# A314B2.net
KiCad netlist of a schematic drawn in EAGLE
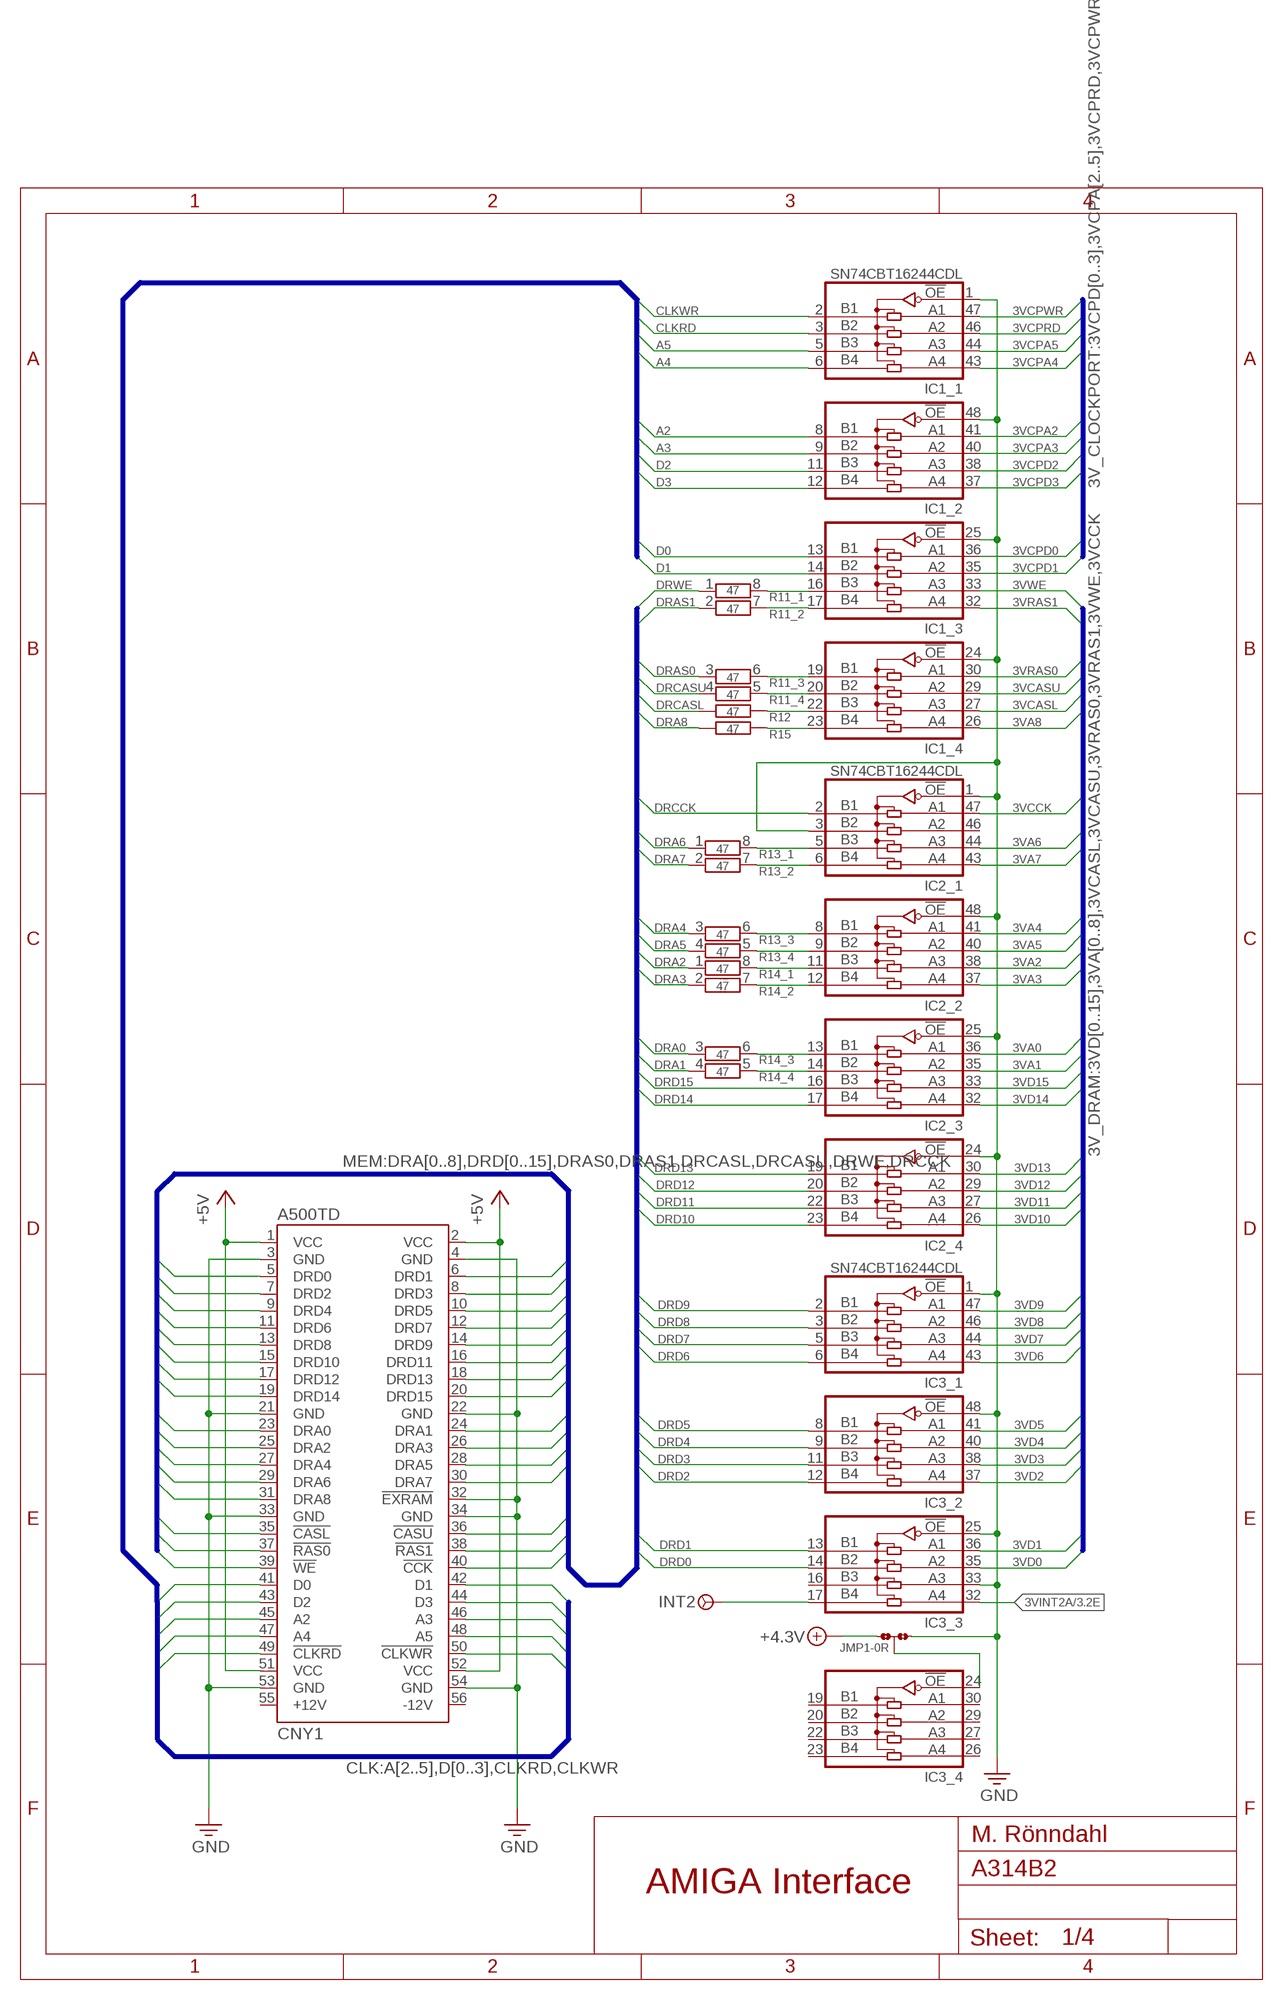
[diagram p0: schematic, sheet 1]
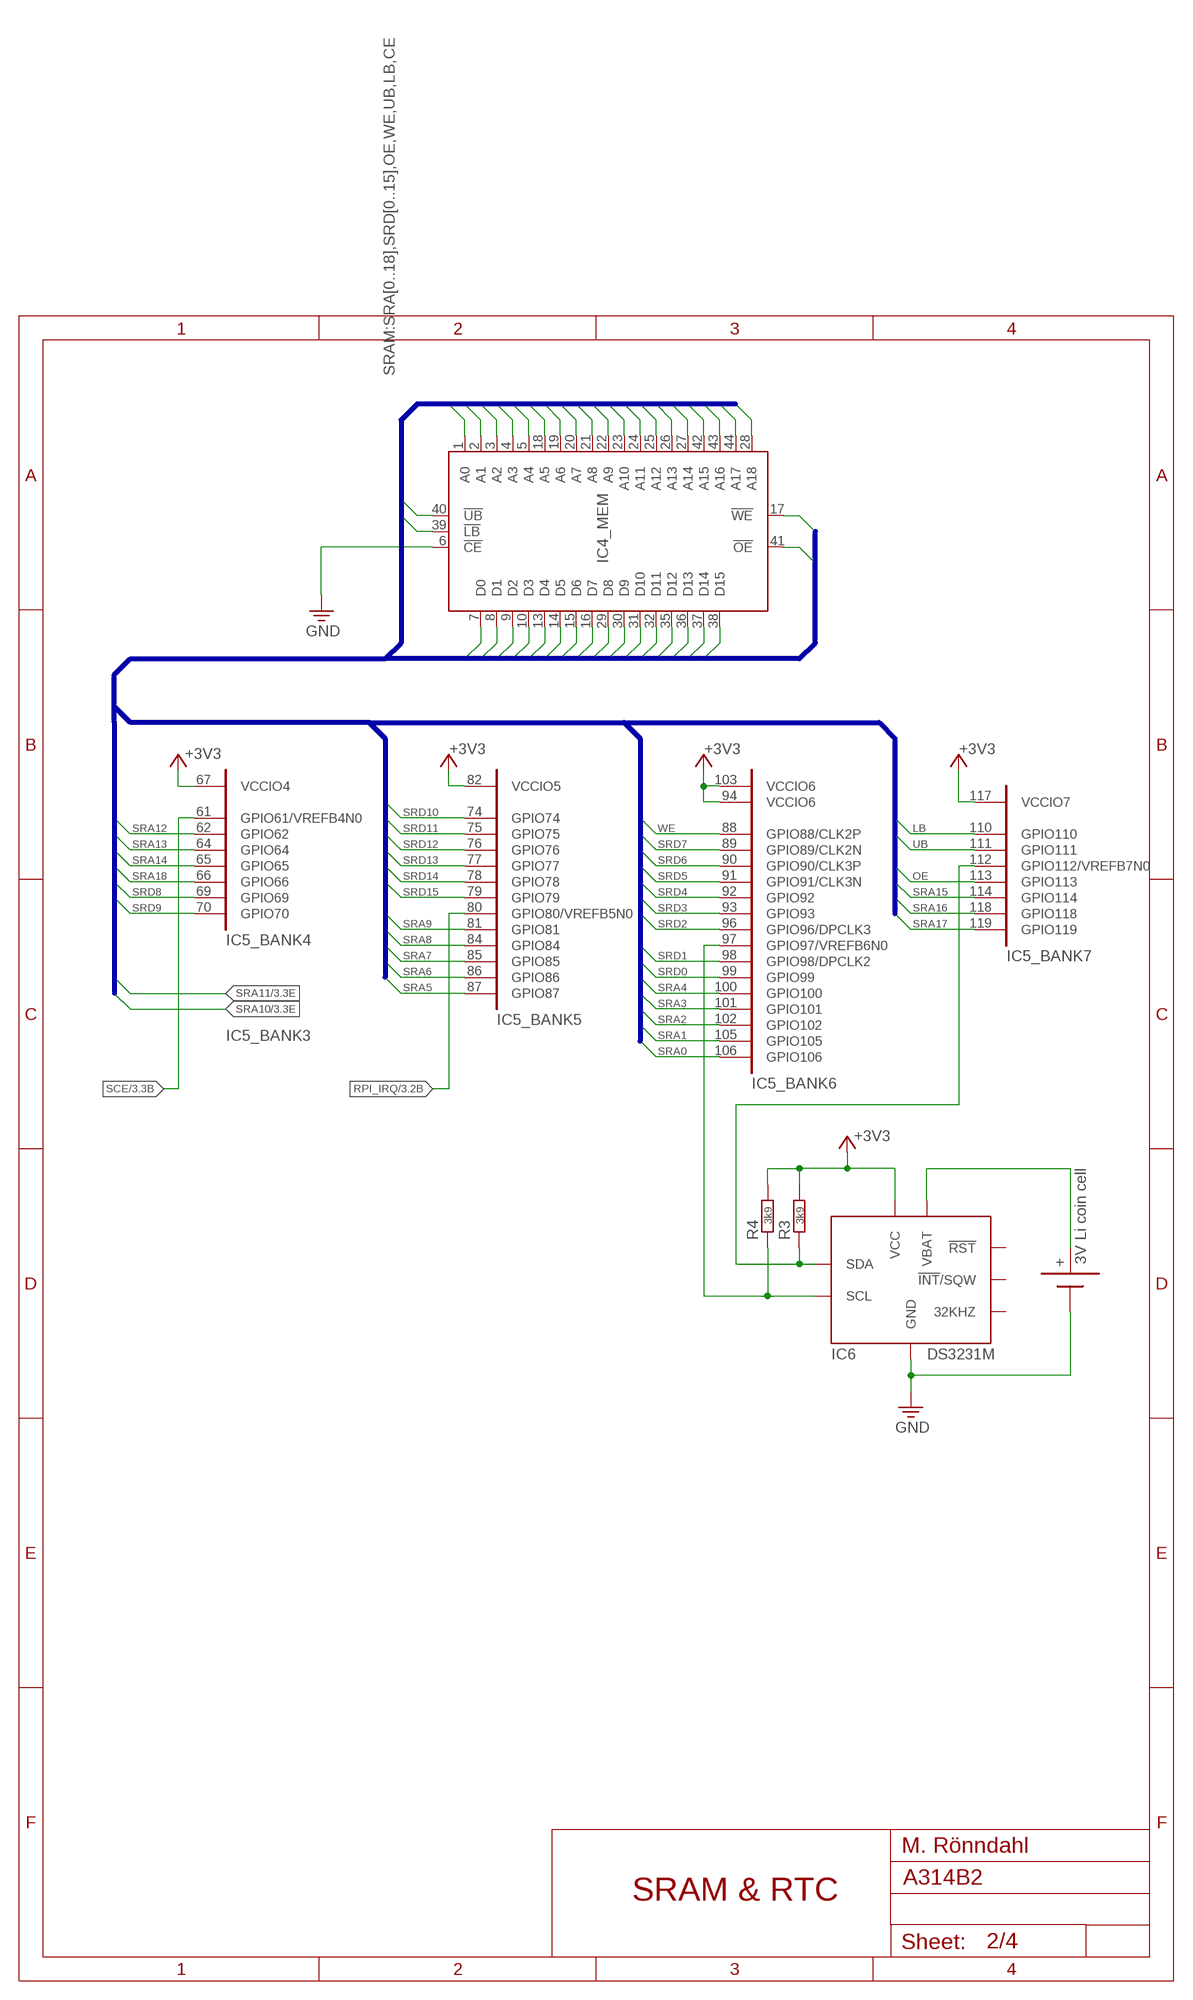
[diagram p1: schematic, sheet 2]
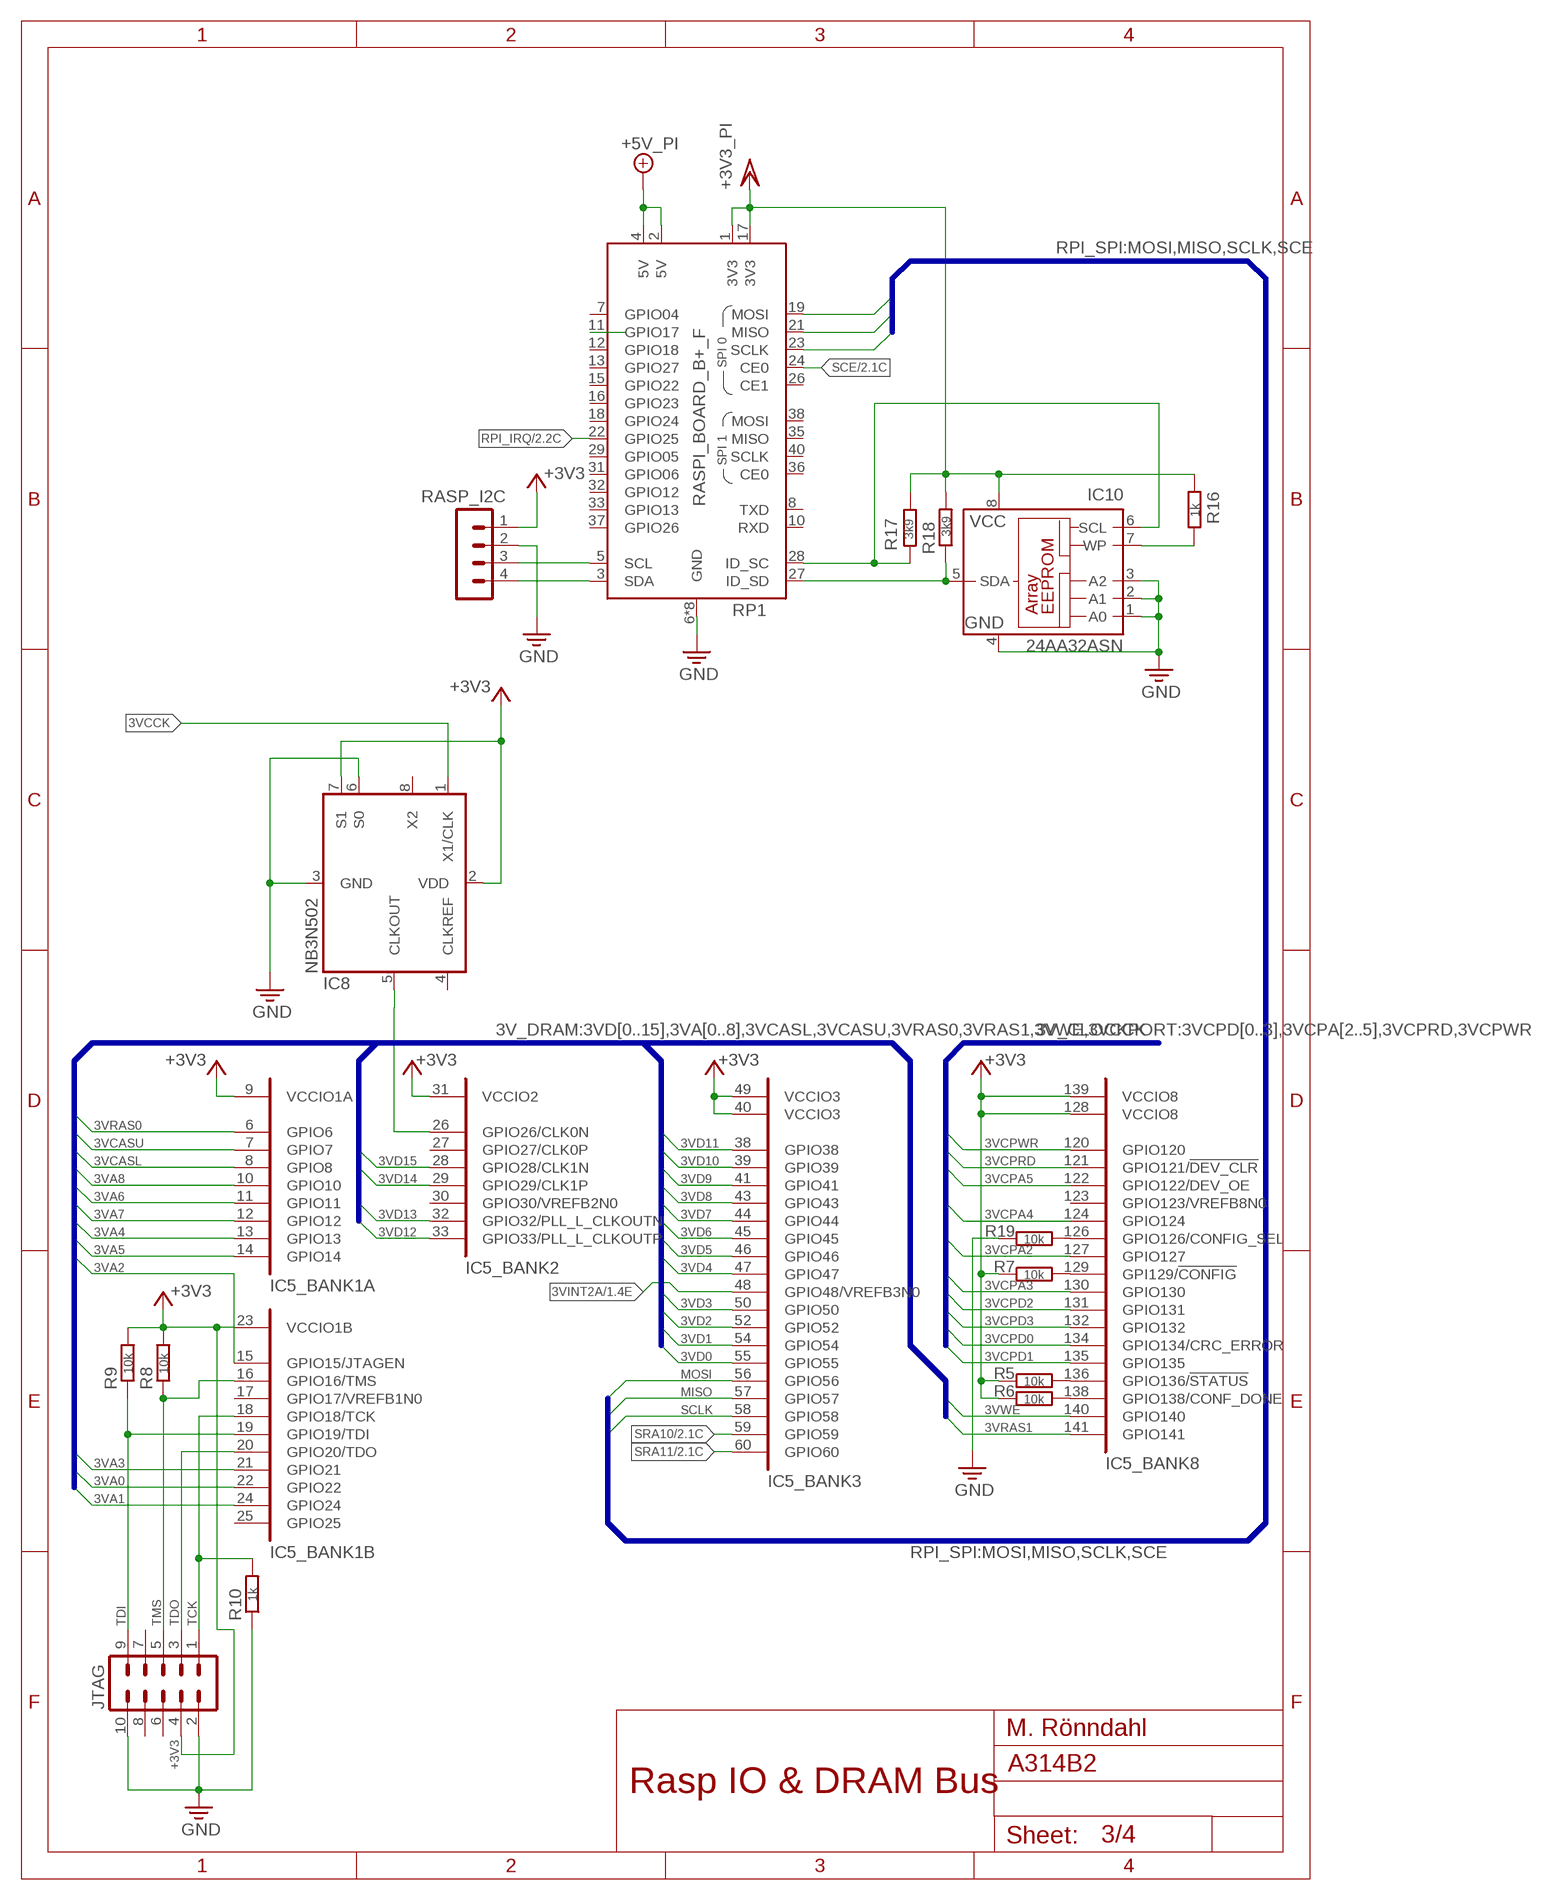
[diagram p2: schematic, sheet 3]
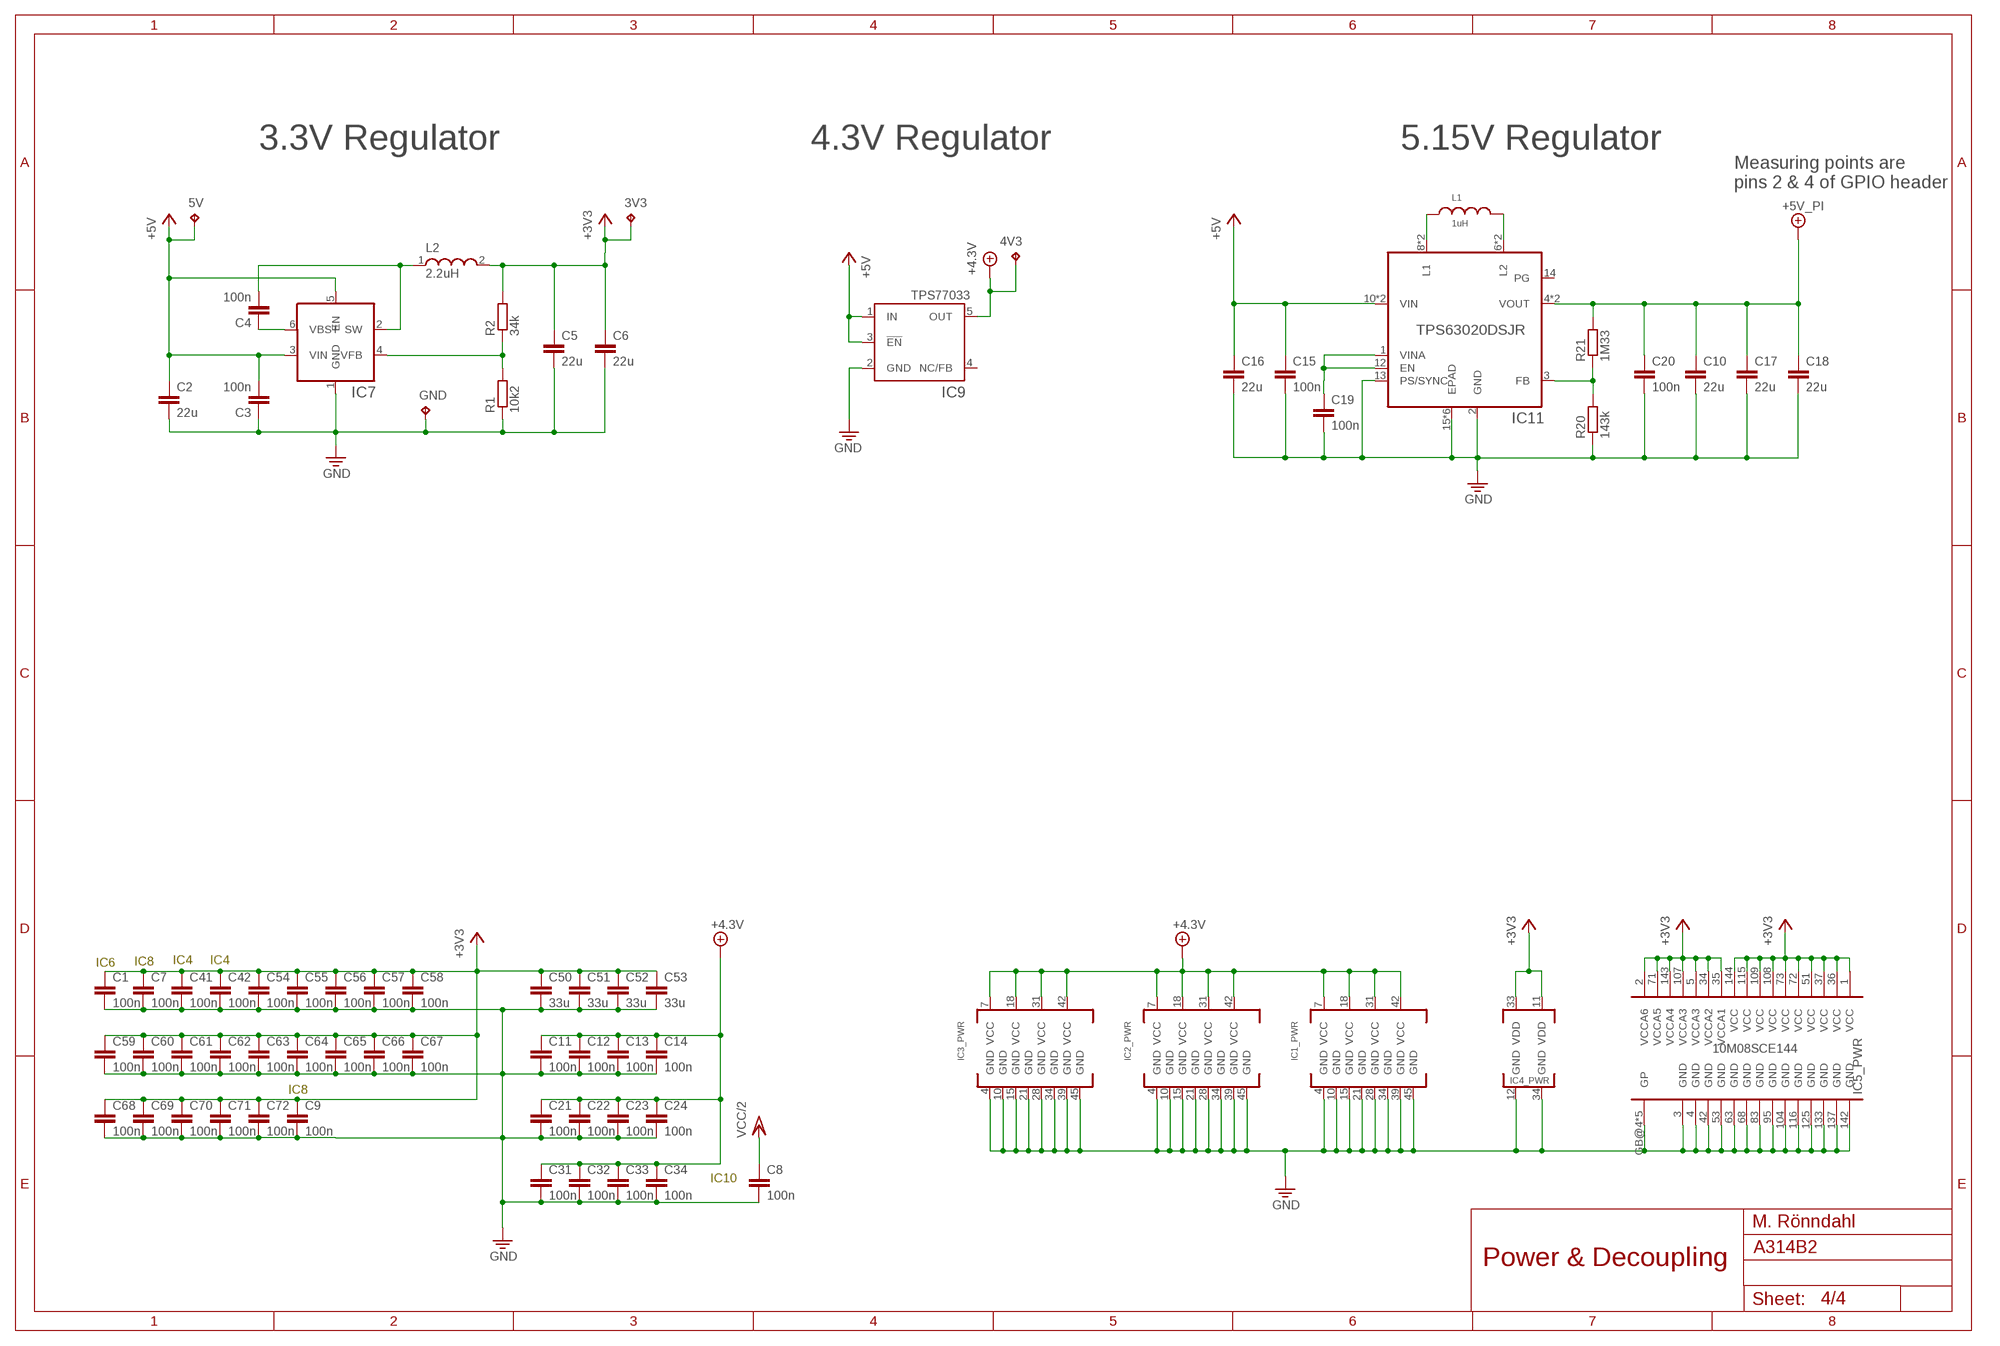
[diagram p3: schematic, sheet 4]

(export (version "E")
  (design (tool "Eeschema 10.0.6"))
  (components
    (comp (ref "CNY1")
      (value "A500TD")
      (footprint "eagle-import:TRAPDOOR")
      (libsource (lib "eagle-import") (part "A500TD"))
    )
    (comp (ref "IC1")
      (value "SN74CBT16244CDL")
      (footprint "eagle-import:SSOP-DL48")
      (libsource (lib "eagle-import") (part "SN74CBT16244CDL"))
    )
    (comp (ref "IC2")
      (value "SN74CBT16244CDL")
      (footprint "eagle-import:SSOP-DL48")
      (libsource (lib "eagle-import") (part "SN74CBT16244CDL"))
    )
    (comp (ref "IC3")
      (value "SN74CBT16244CDL")
      (footprint "eagle-import:SSOP-DL48")
      (libsource (lib "eagle-import") (part "SN74CBT16244CDL"))
    )
    (comp (ref "INT2")
      (value "TP1")
      (footprint "eagle-import:P1-08")
      (libsource (lib "eagle-import") (part "TP_LITE"))
    )
    (comp (ref "JMP1")
      (value "0R-JUMPC")
      (footprint "eagle-import:C0R-JMP")
      (libsource (lib "eagle-import") (part "0R-JUMPC"))
    )
    (comp (ref "R11")
      (value "47")
      (footprint "eagle-import:CTS742C083")
      (libsource (lib "eagle-import") (part "CTS742C083_S"))
    )
    (comp (ref "R12")
      (value "47")
      (footprint "eagle-import:R0805")
      (libsource (lib "eagle-import") (part "R-EU_R0805"))
    )
    (comp (ref "R13")
      (value "47")
      (footprint "eagle-import:CTS742C083")
      (libsource (lib "eagle-import") (part "CTS742C083_S"))
    )
    (comp (ref "R14")
      (value "47")
      (footprint "eagle-import:CTS742C083")
      (libsource (lib "eagle-import") (part "CTS742C083_S"))
    )
    (comp (ref "R15")
      (value "47")
      (footprint "eagle-import:R0805")
      (libsource (lib "eagle-import") (part "R-EU_R0805"))
    )
    (comp (ref "3V3")
      (value "TPPAD1-13")
      (footprint "eagle-import:P1-13")
      (libsource (lib "eagle-import") (part "TPPAD1-13"))
    )
    (comp (ref "4V3")
      (value "TPPAD1-13")
      (footprint "eagle-import:P1-13")
      (libsource (lib "eagle-import") (part "TPPAD1-13"))
    )
    (comp (ref "5V")
      (value "TPPAD1-13")
      (footprint "eagle-import:P1-13")
      (libsource (lib "eagle-import") (part "TPPAD1-13"))
    )
    (comp (ref "C1")
      (value "100n")
      (footprint "eagle-import:C0805")
      (libsource (lib "eagle-import") (part "C-EUC0805"))
    )
    (comp (ref "C2")
      (value "22u")
      (footprint "eagle-import:C1812K")
      (libsource (lib "eagle-import") (part "C-EUC1812K"))
    )
    (comp (ref "C3")
      (value "100n")
      (footprint "eagle-import:C0805")
      (libsource (lib "eagle-import") (part "C-EUC0805"))
    )
    (comp (ref "C4")
      (value "100n")
      (footprint "eagle-import:C0805")
      (libsource (lib "eagle-import") (part "C-EUC0805"))
    )
    (comp (ref "C5")
      (value "22u")
      (footprint "eagle-import:C1812K")
      (libsource (lib "eagle-import") (part "C-EUC1812K"))
    )
    (comp (ref "C6")
      (value "22u")
      (footprint "eagle-import:C1812K")
      (libsource (lib "eagle-import") (part "C-EUC1812K"))
    )
    (comp (ref "C7")
      (value "100n")
      (footprint "eagle-import:C0805")
      (libsource (lib "eagle-import") (part "C-EUC0805"))
    )
    (comp (ref "C8")
      (value "100n")
      (footprint "eagle-import:C0805")
      (libsource (lib "eagle-import") (part "C-EUC0805"))
    )
    (comp (ref "C9")
      (value "100n")
      (footprint "eagle-import:C0805")
      (libsource (lib "eagle-import") (part "C-EUC0805"))
    )
    (comp (ref "C10")
      (value "22u")
      (footprint "eagle-import:C1812K")
      (libsource (lib "eagle-import") (part "C-EUC1812K"))
    )
    (comp (ref "C11")
      (value "100n")
      (footprint "eagle-import:C0805")
      (libsource (lib "eagle-import") (part "C-EUC0805"))
    )
    (comp (ref "C12")
      (value "100n")
      (footprint "eagle-import:C0805")
      (libsource (lib "eagle-import") (part "C-EUC0805"))
    )
    (comp (ref "C13")
      (value "100n")
      (footprint "eagle-import:C0805")
      (libsource (lib "eagle-import") (part "C-EUC0805"))
    )
    (comp (ref "C14")
      (value "100n")
      (footprint "eagle-import:C0805")
      (libsource (lib "eagle-import") (part "C-EUC0805"))
    )
    (comp (ref "C15")
      (value "100n")
      (footprint "eagle-import:C0805")
      (libsource (lib "eagle-import") (part "C-EUC0805"))
    )
    (comp (ref "C16")
      (value "22u")
      (footprint "eagle-import:C1812K")
      (libsource (lib "eagle-import") (part "C-EUC1812K"))
    )
    (comp (ref "C17")
      (value "22u")
      (footprint "eagle-import:C1812K")
      (libsource (lib "eagle-import") (part "C-EUC1812K"))
    )
    (comp (ref "C18")
      (value "22u")
      (footprint "eagle-import:C1812K")
      (libsource (lib "eagle-import") (part "C-EUC1812K"))
    )
    (comp (ref "C19")
      (value "100n")
      (footprint "eagle-import:C0805")
      (libsource (lib "eagle-import") (part "C-EUC0805"))
    )
    (comp (ref "C20")
      (value "100n")
      (footprint "eagle-import:C0805")
      (libsource (lib "eagle-import") (part "C-EUC0805"))
    )
    (comp (ref "C21")
      (value "100n")
      (footprint "eagle-import:C0805")
      (libsource (lib "eagle-import") (part "C-EUC0805"))
    )
    (comp (ref "C22")
      (value "100n")
      (footprint "eagle-import:C0805")
      (libsource (lib "eagle-import") (part "C-EUC0805"))
    )
    (comp (ref "C23")
      (value "100n")
      (footprint "eagle-import:C0805")
      (libsource (lib "eagle-import") (part "C-EUC0805"))
    )
    (comp (ref "C24")
      (value "100n")
      (footprint "eagle-import:C0805")
      (libsource (lib "eagle-import") (part "C-EUC0805"))
    )
    (comp (ref "C31")
      (value "100n")
      (footprint "eagle-import:C0805")
      (libsource (lib "eagle-import") (part "C-EUC0805"))
    )
    (comp (ref "C32")
      (value "100n")
      (footprint "eagle-import:C0805")
      (libsource (lib "eagle-import") (part "C-EUC0805"))
    )
    (comp (ref "C33")
      (value "100n")
      (footprint "eagle-import:C0805")
      (libsource (lib "eagle-import") (part "C-EUC0805"))
    )
    (comp (ref "C34")
      (value "100n")
      (footprint "eagle-import:C0805")
      (libsource (lib "eagle-import") (part "C-EUC0805"))
    )
    (comp (ref "C41")
      (value "100n")
      (footprint "eagle-import:C0805")
      (libsource (lib "eagle-import") (part "C-EUC0805"))
    )
    (comp (ref "C42")
      (value "100n")
      (footprint "eagle-import:C0805")
      (libsource (lib "eagle-import") (part "C-EUC0805"))
    )
    (comp (ref "C50")
      (value "33u")
      (footprint "eagle-import:C0805")
      (libsource (lib "eagle-import") (part "C-EUC0805"))
    )
    (comp (ref "C51")
      (value "33u")
      (footprint "eagle-import:C0805")
      (libsource (lib "eagle-import") (part "C-EUC0805"))
    )
    (comp (ref "C52")
      (value "33u")
      (footprint "eagle-import:C0805")
      (libsource (lib "eagle-import") (part "C-EUC0805"))
    )
    (comp (ref "C53")
      (value "33u")
      (footprint "eagle-import:C0805")
      (libsource (lib "eagle-import") (part "C-EUC0805"))
    )
    (comp (ref "C54")
      (value "100n")
      (footprint "eagle-import:C0805")
      (libsource (lib "eagle-import") (part "C-EUC0805"))
    )
    (comp (ref "C55")
      (value "100n")
      (footprint "eagle-import:C0805")
      (libsource (lib "eagle-import") (part "C-EUC0805"))
    )
    (comp (ref "C56")
      (value "100n")
      (footprint "eagle-import:C0805")
      (libsource (lib "eagle-import") (part "C-EUC0805"))
    )
    (comp (ref "C57")
      (value "100n")
      (footprint "eagle-import:C0805")
      (libsource (lib "eagle-import") (part "C-EUC0805"))
    )
    (comp (ref "C58")
      (value "100n")
      (footprint "eagle-import:C0805")
      (libsource (lib "eagle-import") (part "C-EUC0805"))
    )
    (comp (ref "C59")
      (value "100n")
      (footprint "eagle-import:C0805")
      (libsource (lib "eagle-import") (part "C-EUC0805"))
    )
    (comp (ref "C60")
      (value "100n")
      (footprint "eagle-import:C0805")
      (libsource (lib "eagle-import") (part "C-EUC0805"))
    )
    (comp (ref "C61")
      (value "100n")
      (footprint "eagle-import:C0805")
      (libsource (lib "eagle-import") (part "C-EUC0805"))
    )
    (comp (ref "C62")
      (value "100n")
      (footprint "eagle-import:C0805")
      (libsource (lib "eagle-import") (part "C-EUC0805"))
    )
    (comp (ref "C63")
      (value "100n")
      (footprint "eagle-import:C0805")
      (libsource (lib "eagle-import") (part "C-EUC0805"))
    )
    (comp (ref "C64")
      (value "100n")
      (footprint "eagle-import:C0805")
      (libsource (lib "eagle-import") (part "C-EUC0805"))
    )
    (comp (ref "C65")
      (value "100n")
      (footprint "eagle-import:C0805")
      (libsource (lib "eagle-import") (part "C-EUC0805"))
    )
    (comp (ref "C66")
      (value "100n")
      (footprint "eagle-import:C0805")
      (libsource (lib "eagle-import") (part "C-EUC0805"))
    )
    (comp (ref "C67")
      (value "100n")
      (footprint "eagle-import:C0805")
      (libsource (lib "eagle-import") (part "C-EUC0805"))
    )
    (comp (ref "C68")
      (value "100n")
      (footprint "eagle-import:C0805")
      (libsource (lib "eagle-import") (part "C-EUC0805"))
    )
    (comp (ref "C69")
      (value "100n")
      (footprint "eagle-import:C0805")
      (libsource (lib "eagle-import") (part "C-EUC0805"))
    )
    (comp (ref "C70")
      (value "100n")
      (footprint "eagle-import:C0805")
      (libsource (lib "eagle-import") (part "C-EUC0805"))
    )
    (comp (ref "C71")
      (value "100n")
      (footprint "eagle-import:C0805")
      (libsource (lib "eagle-import") (part "C-EUC0805"))
    )
    (comp (ref "C72")
      (value "100n")
      (footprint "eagle-import:C0805")
      (libsource (lib "eagle-import") (part "C-EUC0805"))
    )
    (comp (ref "GND")
      (value "TPPAD1-13")
      (footprint "eagle-import:P1-13")
      (libsource (lib "eagle-import") (part "TPPAD1-13"))
    )
    (comp (ref "IC4")
      (value "IS61WV51216BLL-10TLI")
      (footprint "eagle-import:TSOP-2")
      (libsource (lib "eagle-import") (part "IS61WV51216BLL-10TLI"))
    )
    (comp (ref "IC5")
      (value "10M08SCE144")
      (footprint "eagle-import:SQFP-S-20X20-144")
      (libsource (lib "eagle-import") (part "10M08SCE144"))
    )
    (comp (ref "IC7")
      (value "TPS565208DDC")
      (footprint "eagle-import:THIN_SO23")
      (libsource (lib "eagle-import") (part "TPS565208DDC"))
    )
    (comp (ref "IC9")
      (value "TPS77033")
      (footprint "eagle-import:SOT23-DBV")
      (fields (field (name "MF") "TEXAS INSTRUMENTS") (field (name "MPN") "TPS77033DBVT"))
      (libsource (lib "eagle-import") (part "TPS77033"))
    )
    (comp (ref "IC11")
      (value "TPS63020DSJR")
      (footprint "eagle-import:DSJ14_2P85X1P58")
      (libsource (lib "eagle-import") (part "TPS63020DSJR"))
    )
    (comp (ref "L1")
      (value "1uH")
      (footprint "eagle-import:WE-TPC_6823")
      (libsource (lib "eagle-import") (part "WE-TPC_6823_744062001"))
    )
    (comp (ref "L2")
      (value "2.2uH")
      (footprint "eagle-import:WE-TPC_1028_1038")
      (libsource (lib "eagle-import") (part "WE-TPC_1028/1038"))
    )
    (comp (ref "R1")
      (value "10k2")
      (footprint "eagle-import:R0805")
      (libsource (lib "eagle-import") (part "R-EU_R0805"))
    )
    (comp (ref "R2")
      (value "34k")
      (footprint "eagle-import:R0805")
      (libsource (lib "eagle-import") (part "R-EU_R0805"))
    )
    (comp (ref "R20")
      (value "143k")
      (footprint "eagle-import:R0805")
      (libsource (lib "eagle-import") (part "R-EU_R0805"))
    )
    (comp (ref "R21")
      (value "1M33")
      (footprint "eagle-import:R0805")
      (libsource (lib "eagle-import") (part "R-EU_R0805"))
    )
    (comp (ref "IC8")
      (value "NB3N502")
      (footprint "eagle-import:SO08")
      (libsource (lib "eagle-import") (part "NB3N502"))
    )
    (comp (ref "IC10")
      (value "24AA32ASN")
      (footprint "eagle-import:SO-08")
      (fields (field (name "MF") "MICROCHIP") (field (name "MPN") "24AA32A-I/SN"))
      (libsource (lib "eagle-import") (part "24SNAA32A"))
    )
    (comp (ref "JTAG")
      (value "MA05-2")
      (footprint "eagle-import:MA05-2")
      (libsource (lib "eagle-import") (part "MA05-2"))
    )
    (comp (ref "R5")
      (value "10k")
      (footprint "eagle-import:R0805")
      (libsource (lib "eagle-import") (part "R-EU_R0805"))
    )
    (comp (ref "R6")
      (value "10k")
      (footprint "eagle-import:R0805")
      (libsource (lib "eagle-import") (part "R-EU_R0805"))
    )
    (comp (ref "R7")
      (value "10k")
      (footprint "eagle-import:R0805")
      (libsource (lib "eagle-import") (part "R-EU_R0805"))
    )
    (comp (ref "R8")
      (value "10k")
      (footprint "eagle-import:R0805")
      (libsource (lib "eagle-import") (part "R-EU_R0805"))
    )
    (comp (ref "R9")
      (value "10k")
      (footprint "eagle-import:R0805")
      (libsource (lib "eagle-import") (part "R-EU_R0805"))
    )
    (comp (ref "R10")
      (value "1k")
      (footprint "eagle-import:R0805")
      (libsource (lib "eagle-import") (part "R-EU_R0805"))
    )
    (comp (ref "R16")
      (value "1k")
      (footprint "eagle-import:R0805")
      (libsource (lib "eagle-import") (part "R-EU_R0805"))
    )
    (comp (ref "R17")
      (value "3k9")
      (footprint "eagle-import:R0805")
      (libsource (lib "eagle-import") (part "R-EU_R0805"))
    )
    (comp (ref "R18")
      (value "3k9")
      (footprint "eagle-import:R0805")
      (libsource (lib "eagle-import") (part "R-EU_R0805"))
    )
    (comp (ref "R19")
      (value "10k")
      (footprint "eagle-import:R0805")
      (libsource (lib "eagle-import") (part "R-EU_R0805"))
    )
    (comp (ref "RASP_I2C")
      (value "MA04-1")
      (footprint "eagle-import:MA04-1")
      (libsource (lib "eagle-import") (part "MA04-1"))
    )
    (comp (ref "RP1")
      (value "RASPI_BOARD_B+_F")
      (footprint "eagle-import:RASPI_BOARD_B+_FULL")
      (libsource (lib "eagle-import") (part "RASPI_BOARD_B+_F"))
    )
    (comp (ref "BAT1")
      (value "CR2025/CR2032TH")
      (footprint "eagle-import:LINX20XX-THM")
      (libsource (lib "eagle-import") (part "CR2025/CR2032TH"))
    )
    (comp (ref "IC6")
      (value "DS3231M")
      (footprint "eagle-import:SOIC8")
      (libsource (lib "eagle-import") (part "DS3231M"))
    )
    (comp (ref "R3")
      (value "3k9")
      (footprint "eagle-import:R0805")
      (libsource (lib "eagle-import") (part "R-EU_R0805"))
    )
    (comp (ref "R4")
      (value "3k9")
      (footprint "eagle-import:R0805")
      (libsource (lib "eagle-import") (part "R-EU_R0805"))
    )
  )
  (nets
    (net (code "3") (name "+3V3") (class "Default")
      (node (ref "3V3") (pin "TP") (pinfunction "TP_TP") (pintype "input"))
      (node (ref "C1") (pin "1") (pinfunction "1_1") (pintype "passive"))
      (node (ref "C41") (pin "1") (pinfunction "1_1") (pintype "passive"))
      (node (ref "C42") (pin "1") (pinfunction "1_1") (pintype "passive"))
      (node (ref "C5") (pin "1") (pinfunction "1_1") (pintype "passive"))
      (node (ref "C50") (pin "1") (pinfunction "1_1") (pintype "passive"))
      (node (ref "C51") (pin "1") (pinfunction "1_1") (pintype "passive"))
      (node (ref "C52") (pin "1") (pinfunction "1_1") (pintype "passive"))
      (node (ref "C53") (pin "1") (pinfunction "1_1") (pintype "passive"))
      (node (ref "C54") (pin "1") (pinfunction "1_1") (pintype "passive"))
      (node (ref "C55") (pin "1") (pinfunction "1_1") (pintype "passive"))
      (node (ref "C56") (pin "1") (pinfunction "1_1") (pintype "passive"))
      (node (ref "C57") (pin "1") (pinfunction "1_1") (pintype "passive"))
      (node (ref "C58") (pin "1") (pinfunction "1_1") (pintype "passive"))
      (node (ref "C59") (pin "1") (pinfunction "1_1") (pintype "passive"))
      (node (ref "C6") (pin "1") (pinfunction "1_1") (pintype "passive"))
      (node (ref "C60") (pin "1") (pinfunction "1_1") (pintype "passive"))
      (node (ref "C61") (pin "1") (pinfunction "1_1") (pintype "passive"))
      (node (ref "C62") (pin "1") (pinfunction "1_1") (pintype "passive"))
      (node (ref "C63") (pin "1") (pinfunction "1_1") (pintype "passive"))
      (node (ref "C64") (pin "1") (pinfunction "1_1") (pintype "passive"))
      (node (ref "C65") (pin "1") (pinfunction "1_1") (pintype "passive"))
      (node (ref "C66") (pin "1") (pinfunction "1_1") (pintype "passive"))
      (node (ref "C67") (pin "1") (pinfunction "1_1") (pintype "passive"))
      (node (ref "C68") (pin "1") (pinfunction "1_1") (pintype "passive"))
      (node (ref "C69") (pin "1") (pinfunction "1_1") (pintype "passive"))
      (node (ref "C7") (pin "1") (pinfunction "1_1") (pintype "passive"))
      (node (ref "C70") (pin "1") (pinfunction "1_1") (pintype "passive"))
      (node (ref "C71") (pin "1") (pinfunction "1_1") (pintype "passive"))
      (node (ref "C72") (pin "1") (pinfunction "1_1") (pintype "passive"))
      (node (ref "C9") (pin "1") (pinfunction "1_1") (pintype "passive"))
      (node (ref "IC4") (pin "11") (pinfunction "VDD_11") (pintype "bidirectional"))
      (node (ref "IC4") (pin "33") (pinfunction "VDD_33") (pintype "bidirectional"))
      (node (ref "IC5") (pin "1") (pinfunction "VCC_1") (pintype "power_in"))
      (node (ref "IC5") (pin "103") (pinfunction "VCCIO6_103") (pintype "power_in"))
      (node (ref "IC5") (pin "107") (pinfunction "VCCA3_107") (pintype "power_in"))
      (node (ref "IC5") (pin "108") (pinfunction "VCC_108") (pintype "power_in"))
      (node (ref "IC5") (pin "109") (pinfunction "VCC_109") (pintype "power_in"))
      (node (ref "IC5") (pin "115") (pinfunction "VCC_115") (pintype "power_in"))
      (node (ref "IC5") (pin "117") (pinfunction "VCCIO7_117") (pintype "power_in"))
      (node (ref "IC5") (pin "128") (pinfunction "VCCIO8_128") (pintype "power_in"))
      (node (ref "IC5") (pin "139") (pinfunction "VCCIO8_139") (pintype "power_in"))
      (node (ref "IC5") (pin "143") (pinfunction "VCCA4_143") (pintype "power_in"))
      (node (ref "IC5") (pin "144") (pinfunction "VCC_144") (pintype "power_in"))
      (node (ref "IC5") (pin "2") (pinfunction "VCCA6_2") (pintype "power_in"))
      (node (ref "IC5") (pin "23") (pinfunction "VCCIO1B_23") (pintype "power_in"))
      (node (ref "IC5") (pin "31") (pinfunction "VCCIO2_31") (pintype "power_in"))
      (node (ref "IC5") (pin "34") (pinfunction "VCCA2_34") (pintype "power_in"))
      (node (ref "IC5") (pin "35") (pinfunction "VCCA1_35") (pintype "power_in"))
      (node (ref "IC5") (pin "36") (pinfunction "VCC_36") (pintype "power_in"))
      (node (ref "IC5") (pin "37") (pinfunction "VCC_37") (pintype "power_in"))
      (node (ref "IC5") (pin "40") (pinfunction "VCCIO3_40") (pintype "power_in"))
      (node (ref "IC5") (pin "49") (pinfunction "VCCIO3_49") (pintype "power_in"))
      (node (ref "IC5") (pin "5") (pinfunction "VCCA3_5") (pintype "power_in"))
      (node (ref "IC5") (pin "51") (pinfunction "VCC_51") (pintype "power_in"))
      (node (ref "IC5") (pin "67") (pinfunction "VCCIO4_67") (pintype "power_in"))
      (node (ref "IC5") (pin "71") (pinfunction "VCCA5_71") (pintype "power_in"))
      (node (ref "IC5") (pin "72") (pinfunction "VCC_72") (pintype "power_in"))
      (node (ref "IC5") (pin "73") (pinfunction "VCC_73") (pintype "power_in"))
      (node (ref "IC5") (pin "82") (pinfunction "VCCIO5_82") (pintype "power_in"))
      (node (ref "IC5") (pin "9") (pinfunction "VCCIO1A_9") (pintype "power_in"))
      (node (ref "IC5") (pin "94") (pinfunction "VCCIO6_94") (pintype "power_in"))
      (node (ref "IC6") (pin "2") (pinfunction "VCC_2") (pintype "power_in"))
      (node (ref "IC8") (pin "2") (pinfunction "VDD_2") (pintype "power_in"))
      (node (ref "IC8") (pin "7") (pinfunction "S1_7") (pintype "input"))
      (node (ref "JTAG") (pin "4") (pinfunction "4_4") (pintype "passive"))
      (node (ref "L2") (pin "2") (pinfunction "2_2") (pintype "passive"))
      (node (ref "R2") (pin "2") (pinfunction "2_2") (pintype "passive"))
      (node (ref "R3") (pin "2") (pinfunction "2_2") (pintype "passive"))
      (node (ref "R4") (pin "2") (pinfunction "2_2") (pintype "passive"))
      (node (ref "R5") (pin "1") (pinfunction "1_1") (pintype "passive"))
      (node (ref "R6") (pin "1") (pinfunction "1_1") (pintype "passive"))
      (node (ref "R7") (pin "1") (pinfunction "1_1") (pintype "passive"))
      (node (ref "R8") (pin "2") (pinfunction "2_2") (pintype "passive"))
      (node (ref "R9") (pin "2") (pinfunction "2_2") (pintype "passive"))
      (node (ref "RASP_I2C") (pin "1") (pinfunction "1_1") (pintype "passive"))
    )
    (net (code "4") (name "+4.3V") (class "Default")
      (node (ref "4V3") (pin "TP") (pinfunction "TP_TP") (pintype "input"))
      (node (ref "C11") (pin "1") (pinfunction "1_1") (pintype "passive"))
      (node (ref "C12") (pin "1") (pinfunction "1_1") (pintype "passive"))
      (node (ref "C13") (pin "1") (pinfunction "1_1") (pintype "passive"))
      (node (ref "C14") (pin "1") (pinfunction "1_1") (pintype "passive"))
      (node (ref "C21") (pin "1") (pinfunction "1_1") (pintype "passive"))
      (node (ref "C22") (pin "1") (pinfunction "1_1") (pintype "passive"))
      (node (ref "C23") (pin "1") (pinfunction "1_1") (pintype "passive"))
      (node (ref "C24") (pin "1") (pinfunction "1_1") (pintype "passive"))
      (node (ref "C31") (pin "1") (pinfunction "1_1") (pintype "passive"))
      (node (ref "C32") (pin "1") (pinfunction "1_1") (pintype "passive"))
      (node (ref "C33") (pin "1") (pinfunction "1_1") (pintype "passive"))
      (node (ref "C34") (pin "1") (pinfunction "1_1") (pintype "passive"))
      (node (ref "IC1") (pin "18") (pinfunction "VCC_18") (pintype "power_in"))
      (node (ref "IC1") (pin "31") (pinfunction "VCC_31") (pintype "power_in"))
      (node (ref "IC1") (pin "42") (pinfunction "VCC_42") (pintype "power_in"))
      (node (ref "IC1") (pin "7") (pinfunction "VCC_7") (pintype "power_in"))
      (node (ref "IC2") (pin "18") (pinfunction "VCC_18") (pintype "power_in"))
      (node (ref "IC2") (pin "31") (pinfunction "VCC_31") (pintype "power_in"))
      (node (ref "IC2") (pin "42") (pinfunction "VCC_42") (pintype "power_in"))
      (node (ref "IC2") (pin "7") (pinfunction "VCC_7") (pintype "power_in"))
      (node (ref "IC3") (pin "18") (pinfunction "VCC_18") (pintype "power_in"))
      (node (ref "IC3") (pin "24") (pinfunction "~{OE}_24") (pintype "input"))
      (node (ref "IC3") (pin "31") (pinfunction "VCC_31") (pintype "power_in"))
      (node (ref "IC3") (pin "42") (pinfunction "VCC_42") (pintype "power_in"))
      (node (ref "IC3") (pin "7") (pinfunction "VCC_7") (pintype "power_in"))
      (node (ref "IC9") (pin "5") (pinfunction "OUT_5") (pintype "passive"))
      (node (ref "JMP1") (pin "1") (pinfunction "1_1") (pintype "passive"))
      (node (ref "JMP1") (pin "2") (pinfunction "2_2") (pintype "passive"))
    )
    (net (code "5") (name "+5V") (class "Default")
      (node (ref "5V") (pin "TP") (pinfunction "TP_TP") (pintype "input"))
      (node (ref "C15") (pin "2") (pinfunction "2_2") (pintype "passive"))
      (node (ref "C16") (pin "1") (pinfunction "1_1") (pintype "passive"))
      (node (ref "C2") (pin "1") (pinfunction "1_1") (pintype "passive"))
      (node (ref "C3") (pin "2") (pinfunction "2_2") (pintype "passive"))
      (node (ref "CNY1") (pin "1") (pinfunction "VCC_1") (pintype "power_in"))
      (node (ref "CNY1") (pin "2") (pinfunction "VCC_2") (pintype "power_in"))
      (node (ref "CNY1") (pin "51") (pinfunction "VCC_51") (pintype "power_in"))
      (node (ref "CNY1") (pin "52") (pinfunction "VCC_52") (pintype "power_in"))
      (node (ref "IC11") (pin "10") (pinfunction "VIN_10") (pintype "input"))
      (node (ref "IC11") (pin "11") (pinfunction "VIN_11") (pintype "input"))
      (node (ref "IC7") (pin "3") (pinfunction "VIN_3") (pintype "power_in"))
      (node (ref "IC7") (pin "5") (pinfunction "EN_5") (pintype "input"))
      (node (ref "IC9") (pin "1") (pinfunction "IN_1") (pintype "input"))
      (node (ref "IC9") (pin "3") (pinfunction "~{EN}_3") (pintype "input"))
    )
    (net (code "6") (name "+5V{slash}1") (class "Default")
      (node (ref "C10") (pin "1") (pinfunction "1_1") (pintype "passive"))
      (node (ref "C17") (pin "1") (pinfunction "1_1") (pintype "passive"))
      (node (ref "C18") (pin "1") (pinfunction "1_1") (pintype "passive"))
      (node (ref "C20") (pin "2") (pinfunction "2_2") (pintype "passive"))
      (node (ref "IC11") (pin "4") (pinfunction "VOUT_4") (pintype "output"))
      (node (ref "IC11") (pin "5") (pinfunction "VOUT_5") (pintype "output"))
      (node (ref "R21") (pin "2") (pinfunction "2_2") (pintype "passive"))
      (node (ref "RP1") (pin "2") (pinfunction "5V_2") (pintype "power_in"))
      (node (ref "RP1") (pin "4") (pinfunction "5V_4") (pintype "power_in"))
    )
    (net (code "7") (name "+12V") (class "Default")
      (node (ref "CNY1") (pin "55") (pinfunction "+12V_55") (pintype "power_in"))
    )
    (net (code "8") (name "-12V") (class "Default")
      (node (ref "CNY1") (pin "56") (pinfunction "-12V_56") (pintype "power_in"))
    )
    (net (code "17") (name "3VA0") (class "Default")
      (node (ref "IC2") (pin "36") (pinfunction "A1_36") (pintype "bidirectional"))
      (node (ref "IC5") (pin "22") (pinfunction "GPIO22_22") (pintype "bidirectional"))
    )
    (net (code "18") (name "3VA1") (class "Default")
      (node (ref "IC2") (pin "35") (pinfunction "A2_35") (pintype "bidirectional"))
      (node (ref "IC5") (pin "24") (pinfunction "GPIO24_24") (pintype "bidirectional"))
    )
    (net (code "19") (name "3VA2") (class "Default")
      (node (ref "IC2") (pin "38") (pinfunction "A3_38") (pintype "bidirectional"))
      (node (ref "IC5") (pin "15") (pinfunction "GPIO15/JTAGEN_15") (pintype "bidirectional"))
    )
    (net (code "20") (name "3VA3") (class "Default")
      (node (ref "IC2") (pin "37") (pinfunction "A4_37") (pintype "bidirectional"))
      (node (ref "IC5") (pin "21") (pinfunction "GPIO21_21") (pintype "bidirectional"))
    )
    (net (code "21") (name "3VA4") (class "Default")
      (node (ref "IC2") (pin "41") (pinfunction "A1_41") (pintype "bidirectional"))
      (node (ref "IC5") (pin "13") (pinfunction "GPIO13_13") (pintype "bidirectional"))
    )
    (net (code "22") (name "3VA5") (class "Default")
      (node (ref "IC2") (pin "40") (pinfunction "A2_40") (pintype "bidirectional"))
      (node (ref "IC5") (pin "14") (pinfunction "GPIO14_14") (pintype "bidirectional"))
    )
    (net (code "23") (name "3VA6") (class "Default")
      (node (ref "IC2") (pin "44") (pinfunction "A3_44") (pintype "bidirectional"))
      (node (ref "IC5") (pin "11") (pinfunction "GPIO11_11") (pintype "bidirectional"))
    )
    (net (code "24") (name "3VA7") (class "Default")
      (node (ref "IC2") (pin "43") (pinfunction "A4_43") (pintype "bidirectional"))
      (node (ref "IC5") (pin "12") (pinfunction "GPIO12_12") (pintype "bidirectional"))
    )
    (net (code "25") (name "3VA8") (class "Default")
      (node (ref "IC1") (pin "26") (pinfunction "A4_26") (pintype "bidirectional"))
      (node (ref "IC5") (pin "10") (pinfunction "GPIO10_10") (pintype "bidirectional"))
    )
    (net (code "26") (name "3VCASL") (class "Default")
      (node (ref "IC1") (pin "27") (pinfunction "A3_27") (pintype "bidirectional"))
      (node (ref "IC5") (pin "8") (pinfunction "GPIO8_8") (pintype "bidirectional"))
    )
    (net (code "27") (name "3VCASU") (class "Default")
      (node (ref "IC1") (pin "29") (pinfunction "A2_29") (pintype "bidirectional"))
      (node (ref "IC5") (pin "7") (pinfunction "GPIO7_7") (pintype "bidirectional"))
    )
    (net (code "28") (name "3VCCK") (class "Default")
      (node (ref "IC2") (pin "47") (pinfunction "A1_47") (pintype "bidirectional"))
      (node (ref "IC8") (pin "1") (pinfunction "X1/CLK_1") (pintype "input"))
    )
    (net (code "29") (name "3VCPA2") (class "Default")
      (node (ref "IC1") (pin "41") (pinfunction "A1_41") (pintype "bidirectional"))
      (node (ref "IC5") (pin "127") (pinfunction "GPIO127_127") (pintype "bidirectional"))
    )
    (net (code "30") (name "3VCPA3") (class "Default")
      (node (ref "IC1") (pin "40") (pinfunction "A2_40") (pintype "bidirectional"))
      (node (ref "IC5") (pin "130") (pinfunction "GPIO130_130") (pintype "bidirectional"))
    )
    (net (code "31") (name "3VCPA4") (class "Default")
      (node (ref "IC1") (pin "43") (pinfunction "A4_43") (pintype "bidirectional"))
      (node (ref "IC5") (pin "124") (pinfunction "GPIO124_124") (pintype "bidirectional"))
    )
    (net (code "32") (name "3VCPA5") (class "Default")
      (node (ref "IC1") (pin "44") (pinfunction "A3_44") (pintype "bidirectional"))
      (node (ref "IC5") (pin "122") (pinfunction "GPIO122/DEV_OE_122") (pintype "bidirectional"))
    )
    (net (code "33") (name "3VCPD0") (class "Default")
      (node (ref "IC1") (pin "36") (pinfunction "A1_36") (pintype "bidirectional"))
      (node (ref "IC5") (pin "134") (pinfunction "GPIO134/CRC_ERROR_134") (pintype "bidirectional"))
    )
    (net (code "34") (name "3VCPD1") (class "Default")
      (node (ref "IC1") (pin "35") (pinfunction "A2_35") (pintype "bidirectional"))
      (node (ref "IC5") (pin "135") (pinfunction "GPIO135_135") (pintype "bidirectional"))
    )
    (net (code "35") (name "3VCPD2") (class "Default")
      (node (ref "IC1") (pin "38") (pinfunction "A3_38") (pintype "bidirectional"))
      (node (ref "IC5") (pin "131") (pinfunction "GPIO131_131") (pintype "bidirectional"))
    )
    (net (code "36") (name "3VCPD3") (class "Default")
      (node (ref "IC1") (pin "37") (pinfunction "A4_37") (pintype "bidirectional"))
      (node (ref "IC5") (pin "132") (pinfunction "GPIO132_132") (pintype "bidirectional"))
    )
    (net (code "37") (name "3VCPRD") (class "Default")
      (node (ref "IC1") (pin "46") (pinfunction "A2_46") (pintype "bidirectional"))
      (node (ref "IC5") (pin "121") (pinfunction "GPIO121/~{DEV_CLR}_121") (pintype "bidirectional"))
    )
    (net (code "38") (name "3VCPWR") (class "Default")
      (node (ref "IC1") (pin "47") (pinfunction "A1_47") (pintype "bidirectional"))
      (node (ref "IC5") (pin "120") (pinfunction "GPIO120_120") (pintype "bidirectional"))
    )
    (net (code "39") (name "3VD0") (class "Default")
      (node (ref "IC3") (pin "35") (pinfunction "A2_35") (pintype "bidirectional"))
      (node (ref "IC5") (pin "55") (pinfunction "GPIO55_55") (pintype "bidirectional"))
    )
    (net (code "40") (name "3VD1") (class "Default")
      (node (ref "IC3") (pin "36") (pinfunction "A1_36") (pintype "bidirectional"))
      (node (ref "IC5") (pin "54") (pinfunction "GPIO54_54") (pintype "bidirectional"))
    )
    (net (code "41") (name "3VD2") (class "Default")
      (node (ref "IC3") (pin "37") (pinfunction "A4_37") (pintype "bidirectional"))
      (node (ref "IC5") (pin "52") (pinfunction "GPIO52_52") (pintype "bidirectional"))
    )
    (net (code "42") (name "3VD3") (class "Default")
      (node (ref "IC3") (pin "38") (pinfunction "A3_38") (pintype "bidirectional"))
      (node (ref "IC5") (pin "50") (pinfunction "GPIO50_50") (pintype "bidirectional"))
    )
    (net (code "43") (name "3VD4") (class "Default")
      (node (ref "IC3") (pin "40") (pinfunction "A2_40") (pintype "bidirectional"))
      (node (ref "IC5") (pin "47") (pinfunction "GPIO47_47") (pintype "bidirectional"))
    )
    (net (code "44") (name "3VD5") (class "Default")
      (node (ref "IC3") (pin "41") (pinfunction "A1_41") (pintype "bidirectional"))
      (node (ref "IC5") (pin "46") (pinfunction "GPIO46_46") (pintype "bidirectional"))
    )
    (net (code "45") (name "3VD6") (class "Default")
      (node (ref "IC3") (pin "43") (pinfunction "A4_43") (pintype "bidirectional"))
      (node (ref "IC5") (pin "45") (pinfunction "GPIO45_45") (pintype "bidirectional"))
    )
    (net (code "46") (name "3VD7") (class "Default")
      (node (ref "IC3") (pin "44") (pinfunction "A3_44") (pintype "bidirectional"))
      (node (ref "IC5") (pin "44") (pinfunction "GPIO44_44") (pintype "bidirectional"))
    )
    (net (code "47") (name "3VD8") (class "Default")
      (node (ref "IC3") (pin "46") (pinfunction "A2_46") (pintype "bidirectional"))
      (node (ref "IC5") (pin "43") (pinfunction "GPIO43_43") (pintype "bidirectional"))
    )
    (net (code "48") (name "3VD9") (class "Default")
      (node (ref "IC3") (pin "47") (pinfunction "A1_47") (pintype "bidirectional"))
      (node (ref "IC5") (pin "41") (pinfunction "GPIO41_41") (pintype "bidirectional"))
    )
    (net (code "49") (name "3VD10") (class "Default")
      (node (ref "IC2") (pin "26") (pinfunction "A4_26") (pintype "bidirectional"))
      (node (ref "IC5") (pin "39") (pinfunction "GPIO39_39") (pintype "bidirectional"))
    )
    (net (code "50") (name "3VD11") (class "Default")
      (node (ref "IC2") (pin "27") (pinfunction "A3_27") (pintype "bidirectional"))
      (node (ref "IC5") (pin "38") (pinfunction "GPIO38_38") (pintype "bidirectional"))
    )
    (net (code "51") (name "3VD12") (class "Default")
      (node (ref "IC2") (pin "29") (pinfunction "A2_29") (pintype "bidirectional"))
      (node (ref "IC5") (pin "33") (pinfunction "GPIO33/PLL_L_CLKOUTP_33") (pintype "bidirectional"))
    )
    (net (code "52") (name "3VD13") (class "Default")
      (node (ref "IC2") (pin "30") (pinfunction "A1_30") (pintype "bidirectional"))
      (node (ref "IC5") (pin "32") (pinfunction "GPIO32/PLL_L_CLKOUTN_32") (pintype "bidirectional"))
    )
    (net (code "53") (name "3VD14") (class "Default")
      (node (ref "IC2") (pin "32") (pinfunction "A4_32") (pintype "bidirectional"))
      (node (ref "IC5") (pin "29") (pinfunction "GPIO29/CLK1P_29") (pintype "bidirectional"))
    )
    (net (code "54") (name "3VD15") (class "Default")
      (node (ref "IC2") (pin "33") (pinfunction "A3_33") (pintype "bidirectional"))
      (node (ref "IC5") (pin "28") (pinfunction "GPIO28/CLK1N_28") (pintype "bidirectional"))
    )
    (net (code "55") (name "3VINT2A") (class "Default")
      (node (ref "IC3") (pin "32") (pinfunction "A4_32") (pintype "bidirectional"))
      (node (ref "IC5") (pin "48") (pinfunction "GPIO48/VREFB3N0_48") (pintype "bidirectional"))
    )
    (net (code "56") (name "3VRAS0") (class "Default")
      (node (ref "IC1") (pin "30") (pinfunction "A1_30") (pintype "bidirectional"))
      (node (ref "IC5") (pin "6") (pinfunction "GPIO6_6") (pintype "bidirectional"))
    )
    (net (code "57") (name "3VRAS1") (class "Default")
      (node (ref "IC1") (pin "32") (pinfunction "A4_32") (pintype "bidirectional"))
      (node (ref "IC5") (pin "141") (pinfunction "GPIO141_141") (pintype "bidirectional"))
    )
    (net (code "58") (name "3VWE") (class "Default")
      (node (ref "IC1") (pin "33") (pinfunction "A3_33") (pintype "bidirectional"))
      (node (ref "IC5") (pin "140") (pinfunction "GPIO140_140") (pintype "bidirectional"))
    )
    (net (code "59") (name "A2") (class "Default")
      (node (ref "CNY1") (pin "45") (pinfunction "A2_45") (pintype "output"))
      (node (ref "IC1") (pin "8") (pinfunction "B1_8") (pintype "bidirectional"))
    )
    (net (code "60") (name "A3") (class "Default")
      (node (ref "CNY1") (pin "46") (pinfunction "A3_46") (pintype "output"))
      (node (ref "IC1") (pin "9") (pinfunction "B2_9") (pintype "bidirectional"))
    )
    (net (code "61") (name "A4") (class "Default")
      (node (ref "CNY1") (pin "47") (pinfunction "A4_47") (pintype "output"))
      (node (ref "IC1") (pin "6") (pinfunction "B4_6") (pintype "bidirectional"))
    )
    (net (code "62") (name "A5") (class "Default")
      (node (ref "CNY1") (pin "48") (pinfunction "A5_48") (pintype "output"))
      (node (ref "IC1") (pin "5") (pinfunction "B3_5") (pintype "bidirectional"))
    )
    (net (code "63") (name "CLKRD") (class "Default")
      (node (ref "CNY1") (pin "49") (pinfunction "~{CLKRD}_49") (pintype "output"))
      (node (ref "IC1") (pin "3") (pinfunction "B2_3") (pintype "bidirectional"))
    )
    (net (code "64") (name "CLKWR") (class "Default")
      (node (ref "CNY1") (pin "50") (pinfunction "~{CLKWR}_50") (pintype "output"))
      (node (ref "IC1") (pin "2") (pinfunction "B1_2") (pintype "bidirectional"))
    )
    (net (code "65") (name "D0") (class "Default")
      (node (ref "CNY1") (pin "41") (pinfunction "D0_41") (pintype "bidirectional"))
      (node (ref "IC1") (pin "13") (pinfunction "B1_13") (pintype "bidirectional"))
    )
    (net (code "66") (name "D1") (class "Default")
      (node (ref "CNY1") (pin "42") (pinfunction "D1_42") (pintype "bidirectional"))
      (node (ref "IC1") (pin "14") (pinfunction "B2_14") (pintype "bidirectional"))
    )
    (net (code "67") (name "D2") (class "Default")
      (node (ref "CNY1") (pin "43") (pinfunction "D2_43") (pintype "bidirectional"))
      (node (ref "IC1") (pin "11") (pinfunction "B3_11") (pintype "bidirectional"))
    )
    (net (code "68") (name "D3") (class "Default")
      (node (ref "CNY1") (pin "44") (pinfunction "D3_44") (pintype "bidirectional"))
      (node (ref "IC1") (pin "12") (pinfunction "B4_12") (pintype "bidirectional"))
    )
    (net (code "69") (name "DRA0") (class "Default")
      (node (ref "CNY1") (pin "23") (pinfunction "DRA0_23") (pintype "output"))
      (node (ref "R14") (pin "3") (pinfunction "P$1_3") (pintype "passive"))
    )
    (net (code "70") (name "DRA1") (class "Default")
      (node (ref "CNY1") (pin "24") (pinfunction "DRA1_24") (pintype "output"))
      (node (ref "R14") (pin "4") (pinfunction "P$1_4") (pintype "passive"))
    )
    (net (code "71") (name "DRA2") (class "Default")
      (node (ref "CNY1") (pin "25") (pinfunction "DRA2_25") (pintype "output"))
      (node (ref "R14") (pin "1") (pinfunction "P$1_1") (pintype "passive"))
    )
    (net (code "72") (name "DRA3") (class "Default")
      (node (ref "CNY1") (pin "26") (pinfunction "DRA3_26") (pintype "output"))
      (node (ref "R14") (pin "2") (pinfunction "P$1_2") (pintype "passive"))
    )
    (net (code "73") (name "DRA4") (class "Default")
      (node (ref "CNY1") (pin "27") (pinfunction "DRA4_27") (pintype "output"))
      (node (ref "R13") (pin "3") (pinfunction "P$1_3") (pintype "passive"))
    )
    (net (code "74") (name "DRA5") (class "Default")
      (node (ref "CNY1") (pin "28") (pinfunction "DRA5_28") (pintype "output"))
      (node (ref "R13") (pin "4") (pinfunction "P$1_4") (pintype "passive"))
    )
    (net (code "75") (name "DRA6") (class "Default")
      (node (ref "CNY1") (pin "29") (pinfunction "DRA6_29") (pintype "output"))
      (node (ref "R13") (pin "1") (pinfunction "P$1_1") (pintype "passive"))
    )
    (net (code "76") (name "DRA7") (class "Default")
      (node (ref "CNY1") (pin "30") (pinfunction "DRA7_30") (pintype "output"))
      (node (ref "R13") (pin "2") (pinfunction "P$1_2") (pintype "passive"))
    )
    (net (code "77") (name "DRA8") (class "Default")
      (node (ref "CNY1") (pin "31") (pinfunction "DRA8_31") (pintype "output"))
      (node (ref "R15") (pin "2") (pinfunction "2_2") (pintype "passive"))
    )
    (net (code "78") (name "DRAS0") (class "Default")
      (node (ref "CNY1") (pin "37") (pinfunction "~{RAS0}_37") (pintype "output"))
      (node (ref "R11") (pin "3") (pinfunction "P$1_3") (pintype "passive"))
    )
    (net (code "79") (name "DRAS1") (class "Default")
      (node (ref "CNY1") (pin "38") (pinfunction "~{RAS1}_38") (pintype "output"))
      (node (ref "R11") (pin "2") (pinfunction "P$1_2") (pintype "passive"))
    )
    (net (code "80") (name "DRCASL") (class "Default")
      (node (ref "CNY1") (pin "35") (pinfunction "~{CASL}_35") (pintype "output"))
      (node (ref "R12") (pin "2") (pinfunction "2_2") (pintype "passive"))
    )
    (net (code "81") (name "DRCASU") (class "Default")
      (node (ref "CNY1") (pin "36") (pinfunction "~{CASU}_36") (pintype "output"))
      (node (ref "R11") (pin "4") (pinfunction "P$1_4") (pintype "passive"))
    )
    (net (code "82") (name "DRCCK") (class "Default")
      (node (ref "CNY1") (pin "40") (pinfunction "~{CCK}_40") (pintype "output"))
      (node (ref "IC2") (pin "2") (pinfunction "B1_2") (pintype "bidirectional"))
    )
    (net (code "83") (name "DRD0") (class "Default")
      (node (ref "CNY1") (pin "5") (pinfunction "DRD0_5") (pintype "bidirectional"))
      (node (ref "IC3") (pin "14") (pinfunction "B2_14") (pintype "bidirectional"))
    )
    (net (code "84") (name "DRD1") (class "Default")
      (node (ref "CNY1") (pin "6") (pinfunction "DRD1_6") (pintype "bidirectional"))
      (node (ref "IC3") (pin "13") (pinfunction "B1_13") (pintype "bidirectional"))
    )
    (net (code "85") (name "DRD2") (class "Default")
      (node (ref "CNY1") (pin "7") (pinfunction "DRD2_7") (pintype "bidirectional"))
      (node (ref "IC3") (pin "12") (pinfunction "B4_12") (pintype "bidirectional"))
    )
    (net (code "86") (name "DRD3") (class "Default")
      (node (ref "CNY1") (pin "8") (pinfunction "DRD3_8") (pintype "bidirectional"))
      (node (ref "IC3") (pin "11") (pinfunction "B3_11") (pintype "bidirectional"))
    )
    (net (code "87") (name "DRD4") (class "Default")
      (node (ref "CNY1") (pin "9") (pinfunction "DRD4_9") (pintype "bidirectional"))
      (node (ref "IC3") (pin "9") (pinfunction "B2_9") (pintype "bidirectional"))
    )
    (net (code "88") (name "DRD5") (class "Default")
      (node (ref "CNY1") (pin "10") (pinfunction "DRD5_10") (pintype "bidirectional"))
      (node (ref "IC3") (pin "8") (pinfunction "B1_8") (pintype "bidirectional"))
    )
    (net (code "89") (name "DRD6") (class "Default")
      (node (ref "CNY1") (pin "11") (pinfunction "DRD6_11") (pintype "bidirectional"))
      (node (ref "IC3") (pin "6") (pinfunction "B4_6") (pintype "bidirectional"))
    )
    (net (code "90") (name "DRD7") (class "Default")
      (node (ref "CNY1") (pin "12") (pinfunction "DRD7_12") (pintype "bidirectional"))
      (node (ref "IC3") (pin "5") (pinfunction "B3_5") (pintype "bidirectional"))
    )
    (net (code "91") (name "DRD8") (class "Default")
      (node (ref "CNY1") (pin "13") (pinfunction "DRD8_13") (pintype "bidirectional"))
      (node (ref "IC3") (pin "3") (pinfunction "B2_3") (pintype "bidirectional"))
    )
    (net (code "92") (name "DRD9") (class "Default")
      (node (ref "CNY1") (pin "14") (pinfunction "DRD9_14") (pintype "bidirectional"))
      (node (ref "IC3") (pin "2") (pinfunction "B1_2") (pintype "bidirectional"))
    )
    (net (code "93") (name "DRD10") (class "Default")
      (node (ref "CNY1") (pin "15") (pinfunction "DRD10_15") (pintype "bidirectional"))
      (node (ref "IC2") (pin "23") (pinfunction "B4_23") (pintype "bidirectional"))
    )
    (net (code "94") (name "DRD11") (class "Default")
      (node (ref "CNY1") (pin "16") (pinfunction "DRD11_16") (pintype "bidirectional"))
      (node (ref "IC2") (pin "22") (pinfunction "B3_22") (pintype "bidirectional"))
    )
    (net (code "95") (name "DRD12") (class "Default")
      (node (ref "CNY1") (pin "17") (pinfunction "DRD12_17") (pintype "bidirectional"))
      (node (ref "IC2") (pin "20") (pinfunction "B2_20") (pintype "bidirectional"))
    )
    (net (code "96") (name "DRD13") (class "Default")
      (node (ref "CNY1") (pin "18") (pinfunction "DRD13_18") (pintype "bidirectional"))
      (node (ref "IC2") (pin "19") (pinfunction "B1_19") (pintype "bidirectional"))
    )
    (net (code "97") (name "DRD14") (class "Default")
      (node (ref "CNY1") (pin "19") (pinfunction "DRD14_19") (pintype "bidirectional"))
      (node (ref "IC2") (pin "17") (pinfunction "B4_17") (pintype "bidirectional"))
    )
    (net (code "98") (name "DRD15") (class "Default")
      (node (ref "CNY1") (pin "20") (pinfunction "DRD15_20") (pintype "bidirectional"))
      (node (ref "IC2") (pin "16") (pinfunction "B3_16") (pintype "bidirectional"))
    )
    (net (code "99") (name "DRWE") (class "Default")
      (node (ref "CNY1") (pin "39") (pinfunction "~{WE}_39") (pintype "output"))
      (node (ref "R11") (pin "1") (pinfunction "P$1_1") (pintype "passive"))
    )
    (net (code "100") (name "GND") (class "Default")
      (node (ref "BAT1") (pin "GND") (pinfunction "-_GND") (pintype "power_in"))
      (node (ref "C1") (pin "2") (pinfunction "2_2") (pintype "passive"))
      (node (ref "C10") (pin "2") (pinfunction "2_2") (pintype "passive"))
      (node (ref "C11") (pin "2") (pinfunction "2_2") (pintype "passive"))
      (node (ref "C12") (pin "2") (pinfunction "2_2") (pintype "passive"))
      (node (ref "C13") (pin "2") (pinfunction "2_2") (pintype "passive"))
      (node (ref "C14") (pin "2") (pinfunction "2_2") (pintype "passive"))
      (node (ref "C15") (pin "1") (pinfunction "1_1") (pintype "passive"))
      (node (ref "C16") (pin "2") (pinfunction "2_2") (pintype "passive"))
      (node (ref "C17") (pin "2") (pinfunction "2_2") (pintype "passive"))
      (node (ref "C18") (pin "2") (pinfunction "2_2") (pintype "passive"))
      (node (ref "C19") (pin "1") (pinfunction "1_1") (pintype "passive"))
      (node (ref "C2") (pin "2") (pinfunction "2_2") (pintype "passive"))
      (node (ref "C20") (pin "1") (pinfunction "1_1") (pintype "passive"))
      (node (ref "C21") (pin "2") (pinfunction "2_2") (pintype "passive"))
      (node (ref "C22") (pin "2") (pinfunction "2_2") (pintype "passive"))
      (node (ref "C23") (pin "2") (pinfunction "2_2") (pintype "passive"))
      (node (ref "C24") (pin "2") (pinfunction "2_2") (pintype "passive"))
      (node (ref "C3") (pin "1") (pinfunction "1_1") (pintype "passive"))
      (node (ref "C31") (pin "2") (pinfunction "2_2") (pintype "passive"))
      (node (ref "C32") (pin "2") (pinfunction "2_2") (pintype "passive"))
      (node (ref "C33") (pin "2") (pinfunction "2_2") (pintype "passive"))
      (node (ref "C34") (pin "2") (pinfunction "2_2") (pintype "passive"))
      (node (ref "C41") (pin "2") (pinfunction "2_2") (pintype "passive"))
      (node (ref "C42") (pin "2") (pinfunction "2_2") (pintype "passive"))
      (node (ref "C5") (pin "2") (pinfunction "2_2") (pintype "passive"))
      (node (ref "C50") (pin "2") (pinfunction "2_2") (pintype "passive"))
      (node (ref "C51") (pin "2") (pinfunction "2_2") (pintype "passive"))
      (node (ref "C52") (pin "2") (pinfunction "2_2") (pintype "passive"))
      (node (ref "C53") (pin "2") (pinfunction "2_2") (pintype "passive"))
      (node (ref "C54") (pin "2") (pinfunction "2_2") (pintype "passive"))
      (node (ref "C55") (pin "2") (pinfunction "2_2") (pintype "passive"))
      (node (ref "C56") (pin "2") (pinfunction "2_2") (pintype "passive"))
      (node (ref "C57") (pin "2") (pinfunction "2_2") (pintype "passive"))
      (node (ref "C58") (pin "2") (pinfunction "2_2") (pintype "passive"))
      (node (ref "C59") (pin "2") (pinfunction "2_2") (pintype "passive"))
      (node (ref "C6") (pin "2") (pinfunction "2_2") (pintype "passive"))
      (node (ref "C60") (pin "2") (pinfunction "2_2") (pintype "passive"))
      (node (ref "C61") (pin "2") (pinfunction "2_2") (pintype "passive"))
      (node (ref "C62") (pin "2") (pinfunction "2_2") (pintype "passive"))
      (node (ref "C63") (pin "2") (pinfunction "2_2") (pintype "passive"))
      (node (ref "C64") (pin "2") (pinfunction "2_2") (pintype "passive"))
      (node (ref "C65") (pin "2") (pinfunction "2_2") (pintype "passive"))
      (node (ref "C66") (pin "2") (pinfunction "2_2") (pintype "passive"))
      (node (ref "C67") (pin "2") (pinfunction "2_2") (pintype "passive"))
      (node (ref "C68") (pin "2") (pinfunction "2_2") (pintype "passive"))
      (node (ref "C69") (pin "2") (pinfunction "2_2") (pintype "passive"))
      (node (ref "C7") (pin "2") (pinfunction "2_2") (pintype "passive"))
      (node (ref "C70") (pin "2") (pinfunction "2_2") (pintype "passive"))
      (node (ref "C71") (pin "2") (pinfunction "2_2") (pintype "passive"))
      (node (ref "C72") (pin "2") (pinfunction "2_2") (pintype "passive"))
      (node (ref "C8") (pin "2") (pinfunction "2_2") (pintype "passive"))
      (node (ref "C9") (pin "2") (pinfunction "2_2") (pintype "passive"))
      (node (ref "CNY1") (pin "21") (pinfunction "GND_21") (pintype "power_in"))
      (node (ref "CNY1") (pin "22") (pinfunction "GND_22") (pintype "power_in"))
      (node (ref "CNY1") (pin "3") (pinfunction "GND_3") (pintype "power_in"))
      (node (ref "CNY1") (pin "32") (pinfunction "~{EXRAM}_32") (pintype "input"))
      (node (ref "CNY1") (pin "33") (pinfunction "GND_33") (pintype "power_in"))
      (node (ref "CNY1") (pin "34") (pinfunction "GND_34") (pintype "power_in"))
      (node (ref "CNY1") (pin "4") (pinfunction "GND_4") (pintype "power_in"))
      (node (ref "CNY1") (pin "53") (pinfunction "GND_53") (pintype "power_in"))
      (node (ref "CNY1") (pin "54") (pinfunction "GND_54") (pintype "power_in"))
      (node (ref "GND") (pin "TP") (pinfunction "TP_TP") (pintype "input"))
      (node (ref "IC1") (pin "1") (pinfunction "~{OE}_1") (pintype "input"))
      (node (ref "IC1") (pin "10") (pinfunction "GND_10") (pintype "power_in"))
      (node (ref "IC1") (pin "15") (pinfunction "GND_15") (pintype "power_in"))
      (node (ref "IC1") (pin "21") (pinfunction "GND_21") (pintype "power_in"))
      (node (ref "IC1") (pin "24") (pinfunction "~{OE}_24") (pintype "input"))
      (node (ref "IC1") (pin "25") (pinfunction "~{OE}_25") (pintype "input"))
      (node (ref "IC1") (pin "28") (pinfunction "GND_28") (pintype "power_in"))
      (node (ref "IC1") (pin "34") (pinfunction "GND_34") (pintype "power_in"))
      (node (ref "IC1") (pin "39") (pinfunction "GND_39") (pintype "power_in"))
      (node (ref "IC1") (pin "4") (pinfunction "GND_4") (pintype "power_in"))
      (node (ref "IC1") (pin "45") (pinfunction "GND_45") (pintype "power_in"))
      (node (ref "IC1") (pin "48") (pinfunction "~{OE}_48") (pintype "input"))
      (node (ref "IC10") (pin "1") (pinfunction "A0_1") (pintype "input"))
      (node (ref "IC10") (pin "2") (pinfunction "A1_2") (pintype "input"))
      (node (ref "IC10") (pin "3") (pinfunction "A2_3") (pintype "input"))
      (node (ref "IC10") (pin "4") (pinfunction "GND_4") (pintype "power_in"))
      (node (ref "IC11") (pin "13") (pinfunction "PS/SYNC_13") (pintype "input"))
      (node (ref "IC11") (pin "15") (pinfunction "EPAD_15") (pintype "passive"))
      (node (ref "IC11") (pin "2") (pinfunction "GND_2") (pintype "power_in"))
      (node (ref "IC11") (pin "V_1") (pinfunction "EPAD_V_1") (pintype "passive"))
      (node (ref "IC11") (pin "V_2") (pinfunction "EPAD_V_2") (pintype "passive"))
      (node (ref "IC11") (pin "V_3") (pinfunction "EPAD_V_3") (pintype "passive"))
      (node (ref "IC11") (pin "V_4") (pinfunction "EPAD_V_4") (pintype "passive"))
      (node (ref "IC11") (pin "V_5") (pinfunction "EPAD_V_5") (pintype "passive"))
      (node (ref "IC2") (pin "1") (pinfunction "~{OE}_1") (pintype "input"))
      (node (ref "IC2") (pin "10") (pinfunction "GND_10") (pintype "power_in"))
      (node (ref "IC2") (pin "15") (pinfunction "GND_15") (pintype "power_in"))
      (node (ref "IC2") (pin "21") (pinfunction "GND_21") (pintype "power_in"))
      (node (ref "IC2") (pin "24") (pinfunction "~{OE}_24") (pintype "input"))
      (node (ref "IC2") (pin "25") (pinfunction "~{OE}_25") (pintype "input"))
      (node (ref "IC2") (pin "28") (pinfunction "GND_28") (pintype "power_in"))
      (node (ref "IC2") (pin "3") (pinfunction "B2_3") (pintype "bidirectional"))
      (node (ref "IC2") (pin "34") (pinfunction "GND_34") (pintype "power_in"))
      (node (ref "IC2") (pin "39") (pinfunction "GND_39") (pintype "power_in"))
      (node (ref "IC2") (pin "4") (pinfunction "GND_4") (pintype "power_in"))
      (node (ref "IC2") (pin "45") (pinfunction "GND_45") (pintype "power_in"))
      (node (ref "IC2") (pin "48") (pinfunction "~{OE}_48") (pintype "input"))
      (node (ref "IC3") (pin "1") (pinfunction "~{OE}_1") (pintype "input"))
      (node (ref "IC3") (pin "10") (pinfunction "GND_10") (pintype "power_in"))
      (node (ref "IC3") (pin "15") (pinfunction "GND_15") (pintype "power_in"))
      (node (ref "IC3") (pin "21") (pinfunction "GND_21") (pintype "power_in"))
      (node (ref "IC3") (pin "25") (pinfunction "~{OE}_25") (pintype "input"))
      (node (ref "IC3") (pin "28") (pinfunction "GND_28") (pintype "power_in"))
      (node (ref "IC3") (pin "33") (pinfunction "A3_33") (pintype "bidirectional"))
      (node (ref "IC3") (pin "34") (pinfunction "GND_34") (pintype "power_in"))
      (node (ref "IC3") (pin "39") (pinfunction "GND_39") (pintype "power_in"))
      (node (ref "IC3") (pin "4") (pinfunction "GND_4") (pintype "power_in"))
      (node (ref "IC3") (pin "45") (pinfunction "GND_45") (pintype "power_in"))
      (node (ref "IC3") (pin "48") (pinfunction "~{OE}_48") (pintype "input"))
      (node (ref "IC4") (pin "12") (pinfunction "GND_12") (pintype "bidirectional"))
      (node (ref "IC4") (pin "34") (pinfunction "GND_34") (pintype "bidirectional"))
      (node (ref "IC4") (pin "6") (pinfunction "~{CE}_6") (pintype "input"))
      (node (ref "IC5") (pin "104") (pinfunction "GND_104") (pintype "power_in"))
      (node (ref "IC5") (pin "116") (pinfunction "GND_116") (pintype "power_in"))
      (node (ref "IC5") (pin "125") (pinfunction "GND_125") (pintype "power_in"))
      (node (ref "IC5") (pin "133") (pinfunction "GND_133") (pintype "power_in"))
      (node (ref "IC5") (pin "137") (pinfunction "GND_137") (pintype "power_in"))
      (node (ref "IC5") (pin "142") (pinfunction "GND_142") (pintype "power_in"))
      (node (ref "IC5") (pin "3") (pinfunction "GND_3") (pintype "power_in"))
      (node (ref "IC5") (pin "4") (pinfunction "GND_4") (pintype "power_in"))
      (node (ref "IC5") (pin "42") (pinfunction "GND_42") (pintype "power_in"))
      (node (ref "IC5") (pin "53") (pinfunction "GND_53") (pintype "power_in"))
      (node (ref "IC5") (pin "63") (pinfunction "GND_63") (pintype "power_in"))
      (node (ref "IC5") (pin "68") (pinfunction "GND_68") (pintype "power_in"))
      (node (ref "IC5") (pin "83") (pinfunction "GND_83") (pintype "power_in"))
      (node (ref "IC5") (pin "95") (pinfunction "GND_95") (pintype "power_in"))
      (node (ref "IC5") (pin "GB@4") (pinfunction "GP_GB@4") (pintype "power_in"))
      (node (ref "IC5") (pin "GP@1") (pinfunction "GP_GP@1") (pintype "power_in"))
      (node (ref "IC5") (pin "GP@2") (pinfunction "GP_GP@2") (pintype "power_in"))
      (node (ref "IC5") (pin "GP@3") (pinfunction "GP_GP@3") (pintype "power_in"))
      (node (ref "IC5") (pin "GP@5") (pinfunction "GP_GP@5") (pintype "power_in"))
      (node (ref "IC6") (pin "5") (pinfunction "GND_5") (pintype "power_in"))
      (node (ref "IC7") (pin "1") (pinfunction "GND_1") (pintype "power_in"))
      (node (ref "IC8") (pin "3") (pinfunction "GND_3") (pintype "power_in"))
      (node (ref "IC8") (pin "6") (pinfunction "S0_6") (pintype "input"))
      (node (ref "IC9") (pin "2") (pinfunction "GND_2") (pintype "power_in"))
      (node (ref "JMP1") (pin "3") (pinfunction "3_3") (pintype "passive"))
      (node (ref "JTAG") (pin "10") (pinfunction "10_10") (pintype "passive"))
      (node (ref "JTAG") (pin "2") (pinfunction "2_2") (pintype "passive"))
      (node (ref "R1") (pin "1") (pinfunction "1_1") (pintype "passive"))
      (node (ref "R10") (pin "1") (pinfunction "1_1") (pintype "passive"))
      (node (ref "R19") (pin "1") (pinfunction "1_1") (pintype "passive"))
      (node (ref "R20") (pin "1") (pinfunction "1_1") (pintype "passive"))
      (node (ref "RASP_I2C") (pin "2") (pinfunction "2_2") (pintype "passive"))
      (node (ref "RP1") (pin "14") (pinfunction "GND_14") (pintype "power_in"))
      (node (ref "RP1") (pin "20") (pinfunction "GND_20") (pintype "power_in"))
      (node (ref "RP1") (pin "25") (pinfunction "GND_25") (pintype "power_in"))
      (node (ref "RP1") (pin "30") (pinfunction "GND_30") (pintype "power_in"))
      (node (ref "RP1") (pin "34") (pinfunction "GND_34") (pintype "power_in"))
      (node (ref "RP1") (pin "39") (pinfunction "GND_39") (pintype "power_in"))
      (node (ref "RP1") (pin "6") (pinfunction "GND_6") (pintype "power_in"))
      (node (ref "RP1") (pin "9") (pinfunction "GND_9") (pintype "power_in"))
    )
    (net (code "101") (name "LB") (class "Default")
      (node (ref "IC4") (pin "39") (pinfunction "~{LB}_39") (pintype "input"))
      (node (ref "IC5") (pin "110") (pinfunction "GPIO110_110") (pintype "bidirectional"))
    )
    (net (code "102") (name "MISO") (class "Default")
      (node (ref "IC5") (pin "57") (pinfunction "GPIO57_57") (pintype "bidirectional"))
      (node (ref "RP1") (pin "21") (pinfunction "MISO_21") (pintype "bidirectional"))
    )
    (net (code "103") (name "MOSI") (class "Default")
      (node (ref "IC5") (pin "56") (pinfunction "GPIO56_56") (pintype "bidirectional"))
      (node (ref "RP1") (pin "19") (pinfunction "MOSI_19") (pintype "bidirectional"))
    )
    (net (code "104") (name "Net-(IC1C-B3)") (class "Default")
      (node (ref "IC1") (pin "16") (pinfunction "B3_16") (pintype "bidirectional"))
      (node (ref "R11") (pin "8") (pinfunction "P$2_8") (pintype "passive"))
    )
    (net (code "105") (name "Net-(IC1C-B4)") (class "Default")
      (node (ref "IC1") (pin "17") (pinfunction "B4_17") (pintype "bidirectional"))
      (node (ref "R11") (pin "7") (pinfunction "P$2_7") (pintype "passive"))
    )
    (net (code "106") (name "Net-(IC1D-B1)") (class "Default")
      (node (ref "IC1") (pin "19") (pinfunction "B1_19") (pintype "bidirectional"))
      (node (ref "R11") (pin "6") (pinfunction "P$2_6") (pintype "passive"))
    )
    (net (code "107") (name "Net-(IC1D-B2)") (class "Default")
      (node (ref "IC1") (pin "20") (pinfunction "B2_20") (pintype "bidirectional"))
      (node (ref "R11") (pin "5") (pinfunction "P$2_5") (pintype "passive"))
    )
    (net (code "108") (name "Net-(IC1D-B3)") (class "Default")
      (node (ref "IC1") (pin "22") (pinfunction "B3_22") (pintype "bidirectional"))
      (node (ref "R12") (pin "1") (pinfunction "1_1") (pintype "passive"))
    )
    (net (code "109") (name "Net-(IC1D-B4)") (class "Default")
      (node (ref "IC1") (pin "23") (pinfunction "B4_23") (pintype "bidirectional"))
      (node (ref "R15") (pin "1") (pinfunction "1_1") (pintype "passive"))
    )
    (net (code "110") (name "Net-(IC2A-B3)") (class "Default")
      (node (ref "IC2") (pin "5") (pinfunction "B3_5") (pintype "bidirectional"))
      (node (ref "R13") (pin "8") (pinfunction "P$2_8") (pintype "passive"))
    )
    (net (code "111") (name "Net-(IC2A-B4)") (class "Default")
      (node (ref "IC2") (pin "6") (pinfunction "B4_6") (pintype "bidirectional"))
      (node (ref "R13") (pin "7") (pinfunction "P$2_7") (pintype "passive"))
    )
    (net (code "112") (name "Net-(IC2B-B1)") (class "Default")
      (node (ref "IC2") (pin "8") (pinfunction "B1_8") (pintype "bidirectional"))
      (node (ref "R13") (pin "6") (pinfunction "P$2_6") (pintype "passive"))
    )
    (net (code "113") (name "Net-(IC2B-B2)") (class "Default")
      (node (ref "IC2") (pin "9") (pinfunction "B2_9") (pintype "bidirectional"))
      (node (ref "R13") (pin "5") (pinfunction "P$2_5") (pintype "passive"))
    )
    (net (code "114") (name "Net-(IC2B-B3)") (class "Default")
      (node (ref "IC2") (pin "11") (pinfunction "B3_11") (pintype "bidirectional"))
      (node (ref "R14") (pin "8") (pinfunction "P$2_8") (pintype "passive"))
    )
    (net (code "115") (name "Net-(IC2B-B4)") (class "Default")
      (node (ref "IC2") (pin "12") (pinfunction "B4_12") (pintype "bidirectional"))
      (node (ref "R14") (pin "7") (pinfunction "P$2_7") (pintype "passive"))
    )
    (net (code "116") (name "Net-(IC2C-B1)") (class "Default")
      (node (ref "IC2") (pin "13") (pinfunction "B1_13") (pintype "bidirectional"))
      (node (ref "R14") (pin "6") (pinfunction "P$2_6") (pintype "passive"))
    )
    (net (code "117") (name "Net-(IC2C-B2)") (class "Default")
      (node (ref "IC2") (pin "14") (pinfunction "B2_14") (pintype "bidirectional"))
      (node (ref "R14") (pin "5") (pinfunction "P$2_5") (pintype "passive"))
    )
    (net (code "118") (name "Net-(IC3C-B4)") (class "Default")
      (node (ref "IC3") (pin "17") (pinfunction "B4_17") (pintype "bidirectional"))
      (node (ref "INT2") (pin "TP") (pinfunction "TP_TP") (pintype "bidirectional"))
    )
    (net (code "119") (name "Net-(IC5C-GPIO26{slash}CLK0N)") (class "Default")
      (node (ref "IC5") (pin "26") (pinfunction "GPIO26/CLK0N_26") (pintype "bidirectional"))
      (node (ref "IC8") (pin "5") (pinfunction "CLKOUT_5") (pintype "output"))
    )
    (net (code "120") (name "Net-(IC5G-GPIO97{slash}VREFB6N0)") (class "Default")
      (node (ref "IC5") (pin "97") (pinfunction "GPIO97/VREFB6N0_97") (pintype "bidirectional"))
      (node (ref "IC6") (pin "8") (pinfunction "SCL_8") (pintype "input"))
      (node (ref "R4") (pin "1") (pinfunction "1_1") (pintype "passive"))
    )
    (net (code "121") (name "Net-(IC5H-GPIO112{slash}VREFB7N0)") (class "Default")
      (node (ref "IC5") (pin "112") (pinfunction "GPIO112/VREFB7N0_112") (pintype "bidirectional"))
      (node (ref "IC6") (pin "7") (pinfunction "SDA_7") (pintype "bidirectional"))
      (node (ref "R3") (pin "1") (pinfunction "1_1") (pintype "passive"))
    )
    (net (code "122") (name "Net-(IC5I-GPI129{slash}~{CONFIG})") (class "Default")
      (node (ref "IC5") (pin "129") (pinfunction "GPI129/~{CONFIG}_129") (pintype "input"))
      (node (ref "R7") (pin "2") (pinfunction "2_2") (pintype "passive"))
    )
    (net (code "123") (name "Net-(IC5I-GPIO126{slash}CONFIG_SEL)") (class "Default")
      (node (ref "IC5") (pin "126") (pinfunction "GPIO126/CONFIG_SEL_126") (pintype "bidirectional"))
      (node (ref "R19") (pin "2") (pinfunction "2_2") (pintype "passive"))
    )
    (net (code "124") (name "Net-(IC5I-GPIO136{slash}~{STATUS})") (class "Default")
      (node (ref "IC5") (pin "136") (pinfunction "GPIO136/~{STATUS}_136") (pintype "bidirectional"))
      (node (ref "R5") (pin "2") (pinfunction "2_2") (pintype "passive"))
    )
    (net (code "125") (name "Net-(IC5I-GPIO138{slash}CONF_DONE)") (class "Default")
      (node (ref "IC5") (pin "138") (pinfunction "GPIO138/CONF_DONE_138") (pintype "bidirectional"))
      (node (ref "R6") (pin "2") (pinfunction "2_2") (pintype "passive"))
    )
    (net (code "126") (name "Net-(IC6-VBAT)") (class "Default")
      (node (ref "BAT1") (pin "+@1") (pinfunction "+_+@1") (pintype "power_in"))
      (node (ref "BAT1") (pin "+@2") (pinfunction "+_+@2") (pintype "power_in"))
      (node (ref "BAT1") (pin "+@3") (pinfunction "+_+@3") (pintype "power_in"))
      (node (ref "BAT1") (pin "+@4") (pinfunction "+_+@4") (pintype "power_in"))
      (node (ref "IC6") (pin "6") (pinfunction "VBAT_6") (pintype "power_in"))
    )
    (net (code "127") (name "Net-(IC7-SW)") (class "Default")
      (node (ref "C4") (pin "2") (pinfunction "2_2") (pintype "passive"))
      (node (ref "IC7") (pin "2") (pinfunction "SW_2") (pintype "power_in"))
      (node (ref "L2") (pin "1") (pinfunction "1_1") (pintype "passive"))
    )
    (net (code "128") (name "Net-(IC7-VBST)") (class "Default")
      (node (ref "C4") (pin "1") (pinfunction "1_1") (pintype "passive"))
      (node (ref "IC7") (pin "6") (pinfunction "VBST_6") (pintype "passive"))
    )
    (net (code "129") (name "Net-(IC7-VFB)") (class "Default")
      (node (ref "IC7") (pin "4") (pinfunction "VFB_4") (pintype "passive"))
      (node (ref "R1") (pin "2") (pinfunction "2_2") (pintype "passive"))
      (node (ref "R2") (pin "1") (pinfunction "1_1") (pintype "passive"))
    )
    (net (code "130") (name "Net-(IC10-SCL)") (class "Default")
      (node (ref "IC10") (pin "6") (pinfunction "SCL_6") (pintype "input"))
      (node (ref "R17") (pin "2") (pinfunction "2_2") (pintype "passive"))
      (node (ref "RP1") (pin "28") (pinfunction "ID_SC_28") (pintype "bidirectional"))
    )
    (net (code "131") (name "Net-(IC10-SDA)") (class "Default")
      (node (ref "IC10") (pin "5") (pinfunction "SDA_5") (pintype "bidirectional"))
      (node (ref "R18") (pin "1") (pinfunction "1_1") (pintype "passive"))
      (node (ref "RP1") (pin "27") (pinfunction "ID_SD_27") (pintype "bidirectional"))
    )
    (net (code "132") (name "Net-(IC10-WP)") (class "Default")
      (node (ref "IC10") (pin "7") (pinfunction "WP_7") (pintype "input"))
      (node (ref "R16") (pin "1") (pinfunction "1_1") (pintype "passive"))
    )
    (net (code "133") (name "Net-(IC11-EN)") (class "Default")
      (node (ref "C19") (pin "2") (pinfunction "2_2") (pintype "passive"))
      (node (ref "IC11") (pin "1") (pinfunction "VINA_1") (pintype "input"))
      (node (ref "IC11") (pin "12") (pinfunction "EN_12") (pintype "input"))
    )
    (net (code "134") (name "Net-(IC11-FB)") (class "Default")
      (node (ref "IC11") (pin "3") (pinfunction "FB_3") (pintype "input"))
      (node (ref "R20") (pin "2") (pinfunction "2_2") (pintype "passive"))
      (node (ref "R21") (pin "1") (pinfunction "1_1") (pintype "passive"))
    )
    (net (code "135") (name "Net-(IC11-L1-Pad8)") (class "Default")
      (node (ref "IC11") (pin "8") (pinfunction "L1_8") (pintype "input"))
      (node (ref "IC11") (pin "9") (pinfunction "L1_9") (pintype "input"))
      (node (ref "L1") (pin "1") (pinfunction "1_1") (pintype "passive"))
    )
    (net (code "136") (name "Net-(IC11-L2-Pad6)") (class "Default")
      (node (ref "IC11") (pin "6") (pinfunction "L2_6") (pintype "input"))
      (node (ref "IC11") (pin "7") (pinfunction "L2_7") (pintype "input"))
      (node (ref "L1") (pin "2") (pinfunction "2_2") (pintype "passive"))
    )
    (net (code "137") (name "Net-(RP1-SCL)") (class "Default")
      (node (ref "RASP_I2C") (pin "3") (pinfunction "3_3") (pintype "passive"))
      (node (ref "RP1") (pin "5") (pinfunction "SCL_5") (pintype "bidirectional"))
    )
    (net (code "138") (name "Net-(RP1-SDA)") (class "Default")
      (node (ref "RASP_I2C") (pin "4") (pinfunction "4_4") (pintype "passive"))
      (node (ref "RP1") (pin "3") (pinfunction "SDA_3") (pintype "bidirectional"))
    )
    (net (code "139") (name "OE") (class "Default")
      (node (ref "IC4") (pin "41") (pinfunction "~{OE}_41") (pintype "input"))
      (node (ref "IC5") (pin "113") (pinfunction "GPIO113_113") (pintype "bidirectional"))
    )
    (net (code "140") (name "RPI_IRQ") (class "Default")
      (node (ref "IC5") (pin "80") (pinfunction "GPIO80/VREFB5N0_80") (pintype "bidirectional"))
      (node (ref "RP1") (pin "22") (pinfunction "GPIO25_22") (pintype "bidirectional"))
    )
    (net (code "141") (name "SCE") (class "Default")
      (node (ref "IC5") (pin "61") (pinfunction "GPIO61/VREFB4N0_61") (pintype "bidirectional"))
      (node (ref "RP1") (pin "24") (pinfunction "CE0_24") (pintype "bidirectional"))
    )
    (net (code "142") (name "SCLK") (class "Default")
      (node (ref "IC5") (pin "58") (pinfunction "GPIO58_58") (pintype "bidirectional"))
      (node (ref "RP1") (pin "23") (pinfunction "SCLK_23") (pintype "bidirectional"))
    )
    (net (code "143") (name "SRA0") (class "Default")
      (node (ref "IC4") (pin "1") (pinfunction "A0_1") (pintype "input"))
      (node (ref "IC5") (pin "106") (pinfunction "GPIO106_106") (pintype "bidirectional"))
    )
    (net (code "144") (name "SRA1") (class "Default")
      (node (ref "IC4") (pin "2") (pinfunction "A1_2") (pintype "input"))
      (node (ref "IC5") (pin "105") (pinfunction "GPIO105_105") (pintype "bidirectional"))
    )
    (net (code "145") (name "SRA2") (class "Default")
      (node (ref "IC4") (pin "3") (pinfunction "A2_3") (pintype "input"))
      (node (ref "IC5") (pin "102") (pinfunction "GPIO102_102") (pintype "bidirectional"))
    )
    (net (code "146") (name "SRA3") (class "Default")
      (node (ref "IC4") (pin "4") (pinfunction "A3_4") (pintype "input"))
      (node (ref "IC5") (pin "101") (pinfunction "GPIO101_101") (pintype "bidirectional"))
    )
    (net (code "147") (name "SRA4") (class "Default")
      (node (ref "IC4") (pin "5") (pinfunction "A4_5") (pintype "input"))
      (node (ref "IC5") (pin "100") (pinfunction "GPIO100_100") (pintype "bidirectional"))
    )
    (net (code "148") (name "SRA5") (class "Default")
      (node (ref "IC4") (pin "18") (pinfunction "A5_18") (pintype "input"))
      (node (ref "IC5") (pin "87") (pinfunction "GPIO87_87") (pintype "bidirectional"))
    )
    (net (code "149") (name "SRA6") (class "Default")
      (node (ref "IC4") (pin "19") (pinfunction "A6_19") (pintype "input"))
      (node (ref "IC5") (pin "86") (pinfunction "GPIO86_86") (pintype "bidirectional"))
    )
    (net (code "150") (name "SRA7") (class "Default")
      (node (ref "IC4") (pin "20") (pinfunction "A7_20") (pintype "input"))
      (node (ref "IC5") (pin "85") (pinfunction "GPIO85_85") (pintype "bidirectional"))
    )
    (net (code "151") (name "SRA8") (class "Default")
      (node (ref "IC4") (pin "21") (pinfunction "A8_21") (pintype "input"))
      (node (ref "IC5") (pin "84") (pinfunction "GPIO84_84") (pintype "bidirectional"))
    )
    (net (code "152") (name "SRA9") (class "Default")
      (node (ref "IC4") (pin "22") (pinfunction "A9_22") (pintype "input"))
      (node (ref "IC5") (pin "81") (pinfunction "GPIO81_81") (pintype "bidirectional"))
    )
    (net (code "153") (name "SRA10") (class "Default")
      (node (ref "IC4") (pin "23") (pinfunction "A10_23") (pintype "input"))
      (node (ref "IC5") (pin "59") (pinfunction "GPIO59_59") (pintype "bidirectional"))
    )
    (net (code "154") (name "SRA11") (class "Default")
      (node (ref "IC4") (pin "24") (pinfunction "A11_24") (pintype "input"))
      (node (ref "IC5") (pin "60") (pinfunction "GPIO60_60") (pintype "bidirectional"))
    )
    (net (code "155") (name "SRA12") (class "Default")
      (node (ref "IC4") (pin "25") (pinfunction "A12_25") (pintype "input"))
      (node (ref "IC5") (pin "62") (pinfunction "GPIO62_62") (pintype "bidirectional"))
    )
    (net (code "156") (name "SRA13") (class "Default")
      (node (ref "IC4") (pin "26") (pinfunction "A13_26") (pintype "input"))
      (node (ref "IC5") (pin "64") (pinfunction "GPIO64_64") (pintype "bidirectional"))
    )
    (net (code "157") (name "SRA14") (class "Default")
      (node (ref "IC4") (pin "27") (pinfunction "A14_27") (pintype "input"))
      (node (ref "IC5") (pin "65") (pinfunction "GPIO65_65") (pintype "bidirectional"))
    )
    (net (code "158") (name "SRA15") (class "Default")
      (node (ref "IC4") (pin "42") (pinfunction "A15_42") (pintype "input"))
      (node (ref "IC5") (pin "114") (pinfunction "GPIO114_114") (pintype "bidirectional"))
    )
    (net (code "159") (name "SRA16") (class "Default")
      (node (ref "IC4") (pin "43") (pinfunction "A16_43") (pintype "input"))
      (node (ref "IC5") (pin "118") (pinfunction "GPIO118_118") (pintype "bidirectional"))
    )
    (net (code "160") (name "SRA17") (class "Default")
      (node (ref "IC4") (pin "44") (pinfunction "A17_44") (pintype "input"))
      (node (ref "IC5") (pin "119") (pinfunction "GPIO119_119") (pintype "bidirectional"))
    )
    (net (code "161") (name "SRA18") (class "Default")
      (node (ref "IC4") (pin "28") (pinfunction "A18_28") (pintype "input"))
      (node (ref "IC5") (pin "66") (pinfunction "GPIO66_66") (pintype "bidirectional"))
    )
    (net (code "162") (name "SRD0") (class "Default")
      (node (ref "IC4") (pin "7") (pinfunction "D0_7") (pintype "bidirectional"))
      (node (ref "IC5") (pin "99") (pinfunction "GPIO99_99") (pintype "bidirectional"))
    )
    (net (code "163") (name "SRD1") (class "Default")
      (node (ref "IC4") (pin "8") (pinfunction "D1_8") (pintype "bidirectional"))
      (node (ref "IC5") (pin "98") (pinfunction "GPIO98/DPCLK2_98") (pintype "bidirectional"))
    )
    (net (code "164") (name "SRD2") (class "Default")
      (node (ref "IC4") (pin "9") (pinfunction "D2_9") (pintype "bidirectional"))
      (node (ref "IC5") (pin "96") (pinfunction "GPIO96/DPCLK3_96") (pintype "bidirectional"))
    )
    (net (code "165") (name "SRD3") (class "Default")
      (node (ref "IC4") (pin "10") (pinfunction "D3_10") (pintype "bidirectional"))
      (node (ref "IC5") (pin "93") (pinfunction "GPIO93_93") (pintype "bidirectional"))
    )
    (net (code "166") (name "SRD4") (class "Default")
      (node (ref "IC4") (pin "13") (pinfunction "D4_13") (pintype "bidirectional"))
      (node (ref "IC5") (pin "92") (pinfunction "GPIO92_92") (pintype "bidirectional"))
    )
    (net (code "167") (name "SRD5") (class "Default")
      (node (ref "IC4") (pin "14") (pinfunction "D5_14") (pintype "bidirectional"))
      (node (ref "IC5") (pin "91") (pinfunction "GPIO91/CLK3N_91") (pintype "bidirectional"))
    )
    (net (code "168") (name "SRD6") (class "Default")
      (node (ref "IC4") (pin "15") (pinfunction "D6_15") (pintype "bidirectional"))
      (node (ref "IC5") (pin "90") (pinfunction "GPIO90/CLK3P_90") (pintype "bidirectional"))
    )
    (net (code "169") (name "SRD7") (class "Default")
      (node (ref "IC4") (pin "16") (pinfunction "D7_16") (pintype "bidirectional"))
      (node (ref "IC5") (pin "89") (pinfunction "GPIO89/CLK2N_89") (pintype "bidirectional"))
    )
    (net (code "170") (name "SRD8") (class "Default")
      (node (ref "IC4") (pin "29") (pinfunction "D8_29") (pintype "bidirectional"))
      (node (ref "IC5") (pin "69") (pinfunction "GPIO69_69") (pintype "bidirectional"))
    )
    (net (code "171") (name "SRD9") (class "Default")
      (node (ref "IC4") (pin "30") (pinfunction "D9_30") (pintype "bidirectional"))
      (node (ref "IC5") (pin "70") (pinfunction "GPIO70_70") (pintype "bidirectional"))
    )
    (net (code "172") (name "SRD10") (class "Default")
      (node (ref "IC4") (pin "31") (pinfunction "D10_31") (pintype "bidirectional"))
      (node (ref "IC5") (pin "74") (pinfunction "GPIO74_74") (pintype "bidirectional"))
    )
    (net (code "173") (name "SRD11") (class "Default")
      (node (ref "IC4") (pin "32") (pinfunction "D11_32") (pintype "bidirectional"))
      (node (ref "IC5") (pin "75") (pinfunction "GPIO75_75") (pintype "bidirectional"))
    )
    (net (code "174") (name "SRD12") (class "Default")
      (node (ref "IC4") (pin "35") (pinfunction "D12_35") (pintype "bidirectional"))
      (node (ref "IC5") (pin "76") (pinfunction "GPIO76_76") (pintype "bidirectional"))
    )
    (net (code "175") (name "SRD13") (class "Default")
      (node (ref "IC4") (pin "36") (pinfunction "D13_36") (pintype "bidirectional"))
      (node (ref "IC5") (pin "77") (pinfunction "GPIO77_77") (pintype "bidirectional"))
    )
    (net (code "176") (name "SRD14") (class "Default")
      (node (ref "IC4") (pin "37") (pinfunction "D14_37") (pintype "bidirectional"))
      (node (ref "IC5") (pin "78") (pinfunction "GPIO78_78") (pintype "bidirectional"))
    )
    (net (code "177") (name "SRD15") (class "Default")
      (node (ref "IC4") (pin "38") (pinfunction "D15_38") (pintype "bidirectional"))
      (node (ref "IC5") (pin "79") (pinfunction "GPIO79_79") (pintype "bidirectional"))
    )
    (net (code "178") (name "TCK") (class "Default")
      (node (ref "IC5") (pin "18") (pinfunction "GPIO18/TCK_18") (pintype "bidirectional"))
      (node (ref "JTAG") (pin "1") (pinfunction "1_1") (pintype "passive"))
      (node (ref "R10") (pin "2") (pinfunction "2_2") (pintype "passive"))
    )
    (net (code "179") (name "TDI") (class "Default")
      (node (ref "IC5") (pin "19") (pinfunction "GPIO19/TDI_19") (pintype "bidirectional"))
      (node (ref "JTAG") (pin "9") (pinfunction "9_9") (pintype "passive"))
      (node (ref "R9") (pin "1") (pinfunction "1_1") (pintype "passive"))
    )
    (net (code "180") (name "TDO") (class "Default")
      (node (ref "IC5") (pin "20") (pinfunction "GPIO20/TDO_20") (pintype "bidirectional"))
      (node (ref "JTAG") (pin "3") (pinfunction "3_3") (pintype "passive"))
    )
    (net (code "181") (name "TMS") (class "Default")
      (node (ref "IC5") (pin "16") (pinfunction "GPIO16/TMS_16") (pintype "bidirectional"))
      (node (ref "JTAG") (pin "5") (pinfunction "5_5") (pintype "passive"))
      (node (ref "R8") (pin "1") (pinfunction "1_1") (pintype "passive"))
    )
    (net (code "182") (name "UB") (class "Default")
      (node (ref "IC4") (pin "40") (pinfunction "~{UB}_40") (pintype "input"))
      (node (ref "IC5") (pin "111") (pinfunction "GPIO111_111") (pintype "bidirectional"))
    )
    (net (code "183") (name "VCC{slash}2") (class "Default")
      (node (ref "C8") (pin "1") (pinfunction "1_1") (pintype "passive"))
      (node (ref "IC10") (pin "8") (pinfunction "VCC_8") (pintype "power_in"))
      (node (ref "R16") (pin "2") (pinfunction "2_2") (pintype "passive"))
      (node (ref "R17") (pin "1") (pinfunction "1_1") (pintype "passive"))
      (node (ref "R18") (pin "2") (pinfunction "2_2") (pintype "passive"))
      (node (ref "RP1") (pin "1") (pinfunction "3V3_1") (pintype "power_in"))
      (node (ref "RP1") (pin "17") (pinfunction "3V3_17") (pintype "power_in"))
    )
    (net (code "184") (name "WE") (class "Default")
      (node (ref "IC4") (pin "17") (pinfunction "~{WE}_17") (pintype "input"))
      (node (ref "IC5") (pin "88") (pinfunction "GPIO88/CLK2P_88") (pintype "bidirectional"))
    )
    (net (code "185") (name "unconnected-(IC2A-A2-Pad46)") (class "Default")
      (node (ref "IC2") (pin "46") (pinfunction "A2_46") (pintype "bidirectional"))
    )
    (net (code "186") (name "unconnected-(IC3C-B3-Pad16)") (class "Default")
      (node (ref "IC3") (pin "16") (pinfunction "B3_16") (pintype "bidirectional"))
    )
    (net (code "187") (name "unconnected-(IC3D-A1-Pad30)") (class "Default")
      (node (ref "IC3") (pin "30") (pinfunction "A1_30") (pintype "bidirectional"))
    )
    (net (code "188") (name "unconnected-(IC3D-A2-Pad29)") (class "Default")
      (node (ref "IC3") (pin "29") (pinfunction "A2_29") (pintype "bidirectional"))
    )
    (net (code "189") (name "unconnected-(IC3D-A3-Pad27)") (class "Default")
      (node (ref "IC3") (pin "27") (pinfunction "A3_27") (pintype "bidirectional"))
    )
    (net (code "190") (name "unconnected-(IC3D-A4-Pad26)") (class "Default")
      (node (ref "IC3") (pin "26") (pinfunction "A4_26") (pintype "bidirectional"))
    )
    (net (code "191") (name "unconnected-(IC3D-B1-Pad19)") (class "Default")
      (node (ref "IC3") (pin "19") (pinfunction "B1_19") (pintype "bidirectional"))
    )
    (net (code "192") (name "unconnected-(IC3D-B2-Pad20)") (class "Default")
      (node (ref "IC3") (pin "20") (pinfunction "B2_20") (pintype "bidirectional"))
    )
    (net (code "193") (name "unconnected-(IC3D-B3-Pad22)") (class "Default")
      (node (ref "IC3") (pin "22") (pinfunction "B3_22") (pintype "bidirectional"))
    )
    (net (code "194") (name "unconnected-(IC3D-B4-Pad23)") (class "Default")
      (node (ref "IC3") (pin "23") (pinfunction "B4_23") (pintype "bidirectional"))
    )
    (net (code "195") (name "unconnected-(IC5B-GPIO17{slash}VREFB1N0-Pad17)") (class "Default")
      (node (ref "IC5") (pin "17") (pinfunction "GPIO17/VREFB1N0_17") (pintype "bidirectional"))
    )
    (net (code "196") (name "unconnected-(IC5B-GPIO25-Pad25)") (class "Default")
      (node (ref "IC5") (pin "25") (pinfunction "GPIO25_25") (pintype "bidirectional"))
    )
    (net (code "197") (name "unconnected-(IC5C-GPIO27{slash}CLK0P-Pad27)") (class "Default")
      (node (ref "IC5") (pin "27") (pinfunction "GPIO27/CLK0P_27") (pintype "bidirectional"))
    )
    (net (code "198") (name "unconnected-(IC5C-GPIO30{slash}VREFB2N0-Pad30)") (class "Default")
      (node (ref "IC5") (pin "30") (pinfunction "GPIO30/VREFB2N0_30") (pintype "bidirectional"))
    )
    (net (code "199") (name "unconnected-(IC5I-GPIO123{slash}VREFB8N0-Pad123)") (class "Default")
      (node (ref "IC5") (pin "123") (pinfunction "GPIO123/VREFB8N0_123") (pintype "bidirectional"))
    )
    (net (code "200") (name "unconnected-(IC6-32KHZ-Pad1)") (class "Default")
      (node (ref "IC6") (pin "1") (pinfunction "32KHZ_1") (pintype "output"))
    )
    (net (code "201") (name "unconnected-(IC6-~{INT}{slash}SQW-Pad3)") (class "Default")
      (node (ref "IC6") (pin "3") (pinfunction "~{INT}/SQW_3") (pintype "output"))
    )
    (net (code "202") (name "unconnected-(IC6-~{RST}-Pad4)") (class "Default")
      (node (ref "IC6") (pin "4") (pinfunction "~{RST}_4") (pintype "input"))
    )
    (net (code "203") (name "unconnected-(IC8-CLKREF-Pad4)") (class "Default")
      (node (ref "IC8") (pin "4") (pinfunction "CLKREF_4") (pintype "output"))
    )
    (net (code "204") (name "unconnected-(IC8-X2-Pad8)") (class "Default")
      (node (ref "IC8") (pin "8") (pinfunction "X2_8") (pintype "input"))
    )
    (net (code "205") (name "unconnected-(IC9-NC{slash}FB-Pad4)") (class "Default")
      (node (ref "IC9") (pin "4") (pinfunction "NC/FB_4") (pintype "passive"))
    )
    (net (code "206") (name "unconnected-(IC11-PG-Pad14)") (class "Default")
      (node (ref "IC11") (pin "14") (pinfunction "PG_14") (pintype "output"))
    )
    (net (code "207") (name "unconnected-(JTAG-Pad6)") (class "Default")
      (node (ref "JTAG") (pin "6") (pinfunction "6_6") (pintype "passive"))
    )
    (net (code "208") (name "unconnected-(JTAG-Pad7)") (class "Default")
      (node (ref "JTAG") (pin "7") (pinfunction "7_7") (pintype "passive"))
    )
    (net (code "209") (name "unconnected-(JTAG-Pad8)") (class "Default")
      (node (ref "JTAG") (pin "8") (pinfunction "8_8") (pintype "passive"))
    )
    (net (code "210") (name "unconnected-(RP1-CE0-Pad36)") (class "Default")
      (node (ref "RP1") (pin "36") (pinfunction "CE0_36") (pintype "bidirectional"))
    )
    (net (code "211") (name "unconnected-(RP1-CE1-Pad26)") (class "Default")
      (node (ref "RP1") (pin "26") (pinfunction "CE1_26") (pintype "bidirectional"))
    )
    (net (code "212") (name "unconnected-(RP1-GPIO04-Pad7)") (class "Default")
      (node (ref "RP1") (pin "7") (pinfunction "GPIO04_7") (pintype "bidirectional"))
    )
    (net (code "213") (name "unconnected-(RP1-GPIO05-Pad29)") (class "Default")
      (node (ref "RP1") (pin "29") (pinfunction "GPIO05_29") (pintype "bidirectional"))
    )
    (net (code "214") (name "unconnected-(RP1-GPIO06-Pad31)") (class "Default")
      (node (ref "RP1") (pin "31") (pinfunction "GPIO06_31") (pintype "bidirectional"))
    )
    (net (code "215") (name "unconnected-(RP1-GPIO12-Pad32)") (class "Default")
      (node (ref "RP1") (pin "32") (pinfunction "GPIO12_32") (pintype "bidirectional"))
    )
    (net (code "216") (name "unconnected-(RP1-GPIO13-Pad33)") (class "Default")
      (node (ref "RP1") (pin "33") (pinfunction "GPIO13_33") (pintype "bidirectional"))
    )
    (net (code "217") (name "unconnected-(RP1-GPIO17-Pad11)") (class "Default")
      (node (ref "RP1") (pin "11") (pinfunction "GPIO17_11") (pintype "bidirectional"))
    )
    (net (code "218") (name "unconnected-(RP1-GPIO18-Pad12)") (class "Default")
      (node (ref "RP1") (pin "12") (pinfunction "GPIO18_12") (pintype "bidirectional"))
    )
    (net (code "219") (name "unconnected-(RP1-GPIO22-Pad15)") (class "Default")
      (node (ref "RP1") (pin "15") (pinfunction "GPIO22_15") (pintype "bidirectional"))
    )
    (net (code "220") (name "unconnected-(RP1-GPIO23-Pad16)") (class "Default")
      (node (ref "RP1") (pin "16") (pinfunction "GPIO23_16") (pintype "bidirectional"))
    )
    (net (code "221") (name "unconnected-(RP1-GPIO24-Pad18)") (class "Default")
      (node (ref "RP1") (pin "18") (pinfunction "GPIO24_18") (pintype "bidirectional"))
    )
    (net (code "222") (name "unconnected-(RP1-GPIO26-Pad37)") (class "Default")
      (node (ref "RP1") (pin "37") (pinfunction "GPIO26_37") (pintype "bidirectional"))
    )
    (net (code "223") (name "unconnected-(RP1-GPIO27-Pad13)") (class "Default")
      (node (ref "RP1") (pin "13") (pinfunction "GPIO27_13") (pintype "bidirectional"))
    )
    (net (code "224") (name "unconnected-(RP1-MISO-Pad35)") (class "Default")
      (node (ref "RP1") (pin "35") (pinfunction "MISO_35") (pintype "bidirectional"))
    )
    (net (code "225") (name "unconnected-(RP1-MOSI-Pad38)") (class "Default")
      (node (ref "RP1") (pin "38") (pinfunction "MOSI_38") (pintype "bidirectional"))
    )
    (net (code "226") (name "unconnected-(RP1-RXD-Pad10)") (class "Default")
      (node (ref "RP1") (pin "10") (pinfunction "RXD_10") (pintype "bidirectional"))
    )
    (net (code "227") (name "unconnected-(RP1-SCLK-Pad40)") (class "Default")
      (node (ref "RP1") (pin "40") (pinfunction "SCLK_40") (pintype "bidirectional"))
    )
    (net (code "228") (name "unconnected-(RP1-TXD-Pad8)") (class "Default")
      (node (ref "RP1") (pin "8") (pinfunction "TXD_8") (pintype "bidirectional"))
    )
  )
)
